# MalO_SAO_EasyEDA.net
KiCad netlist of a schematic drawn in EasyEDA Pro
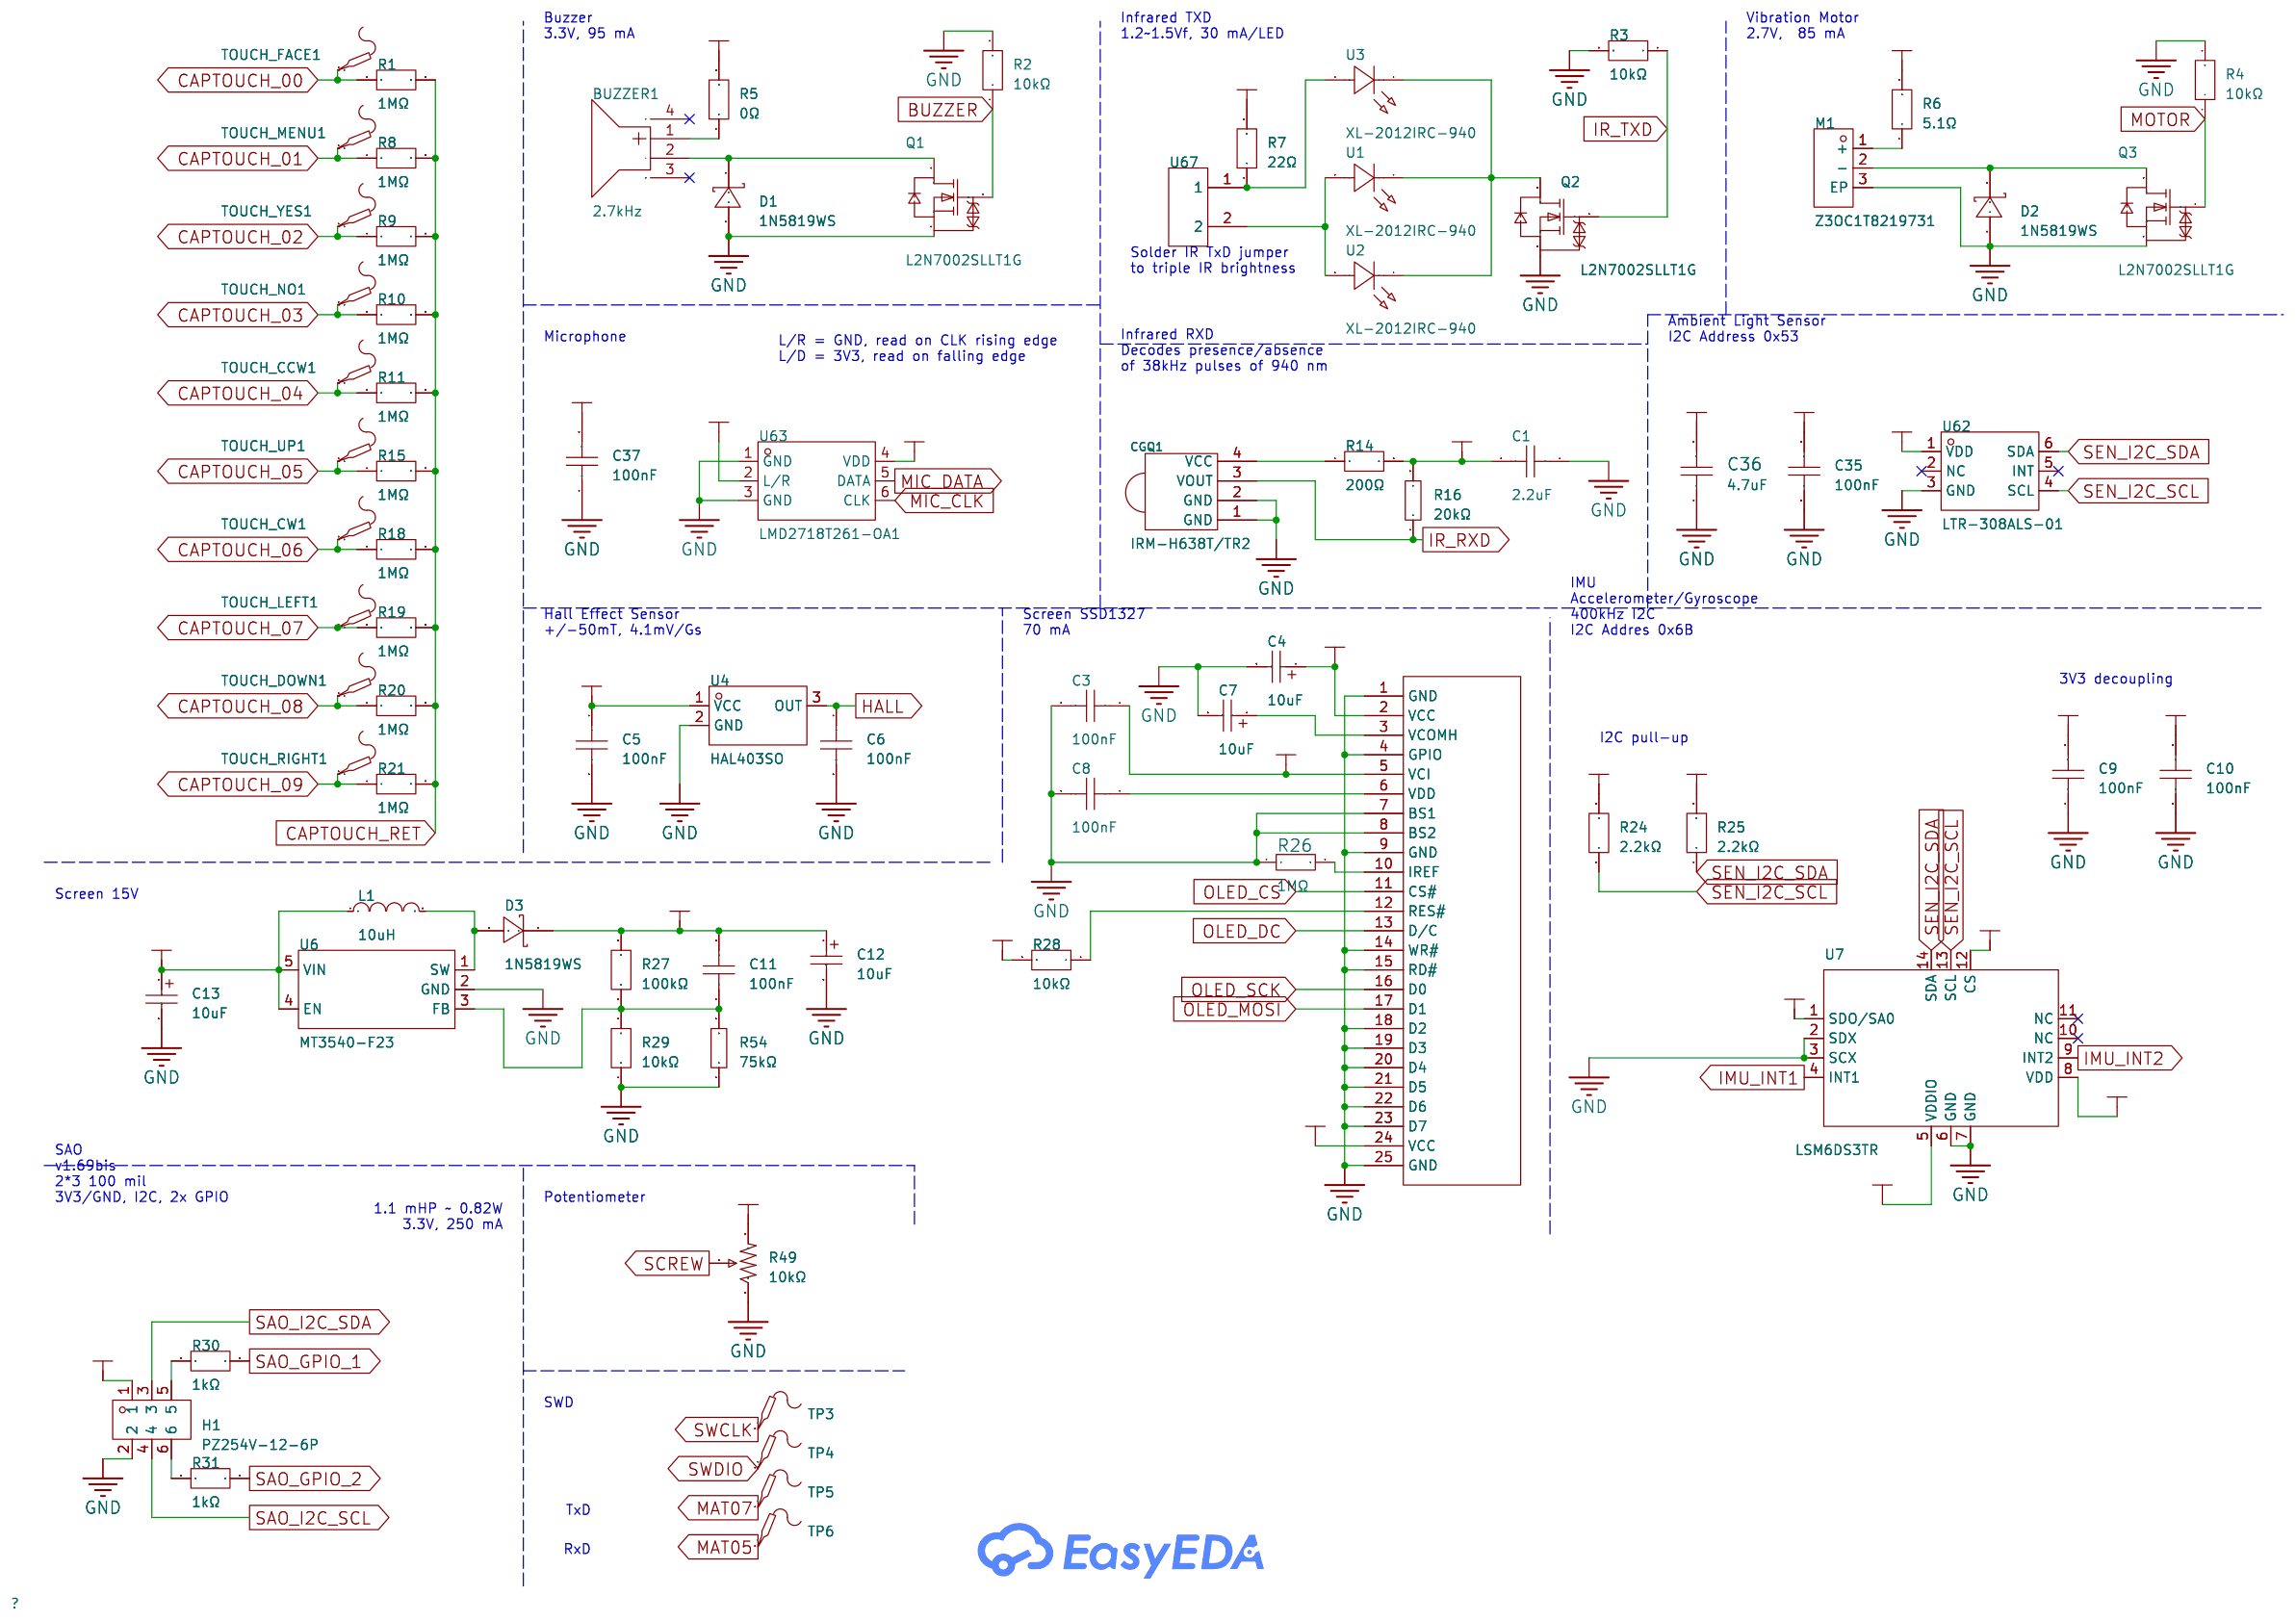
[diagram p0: Periphreals]
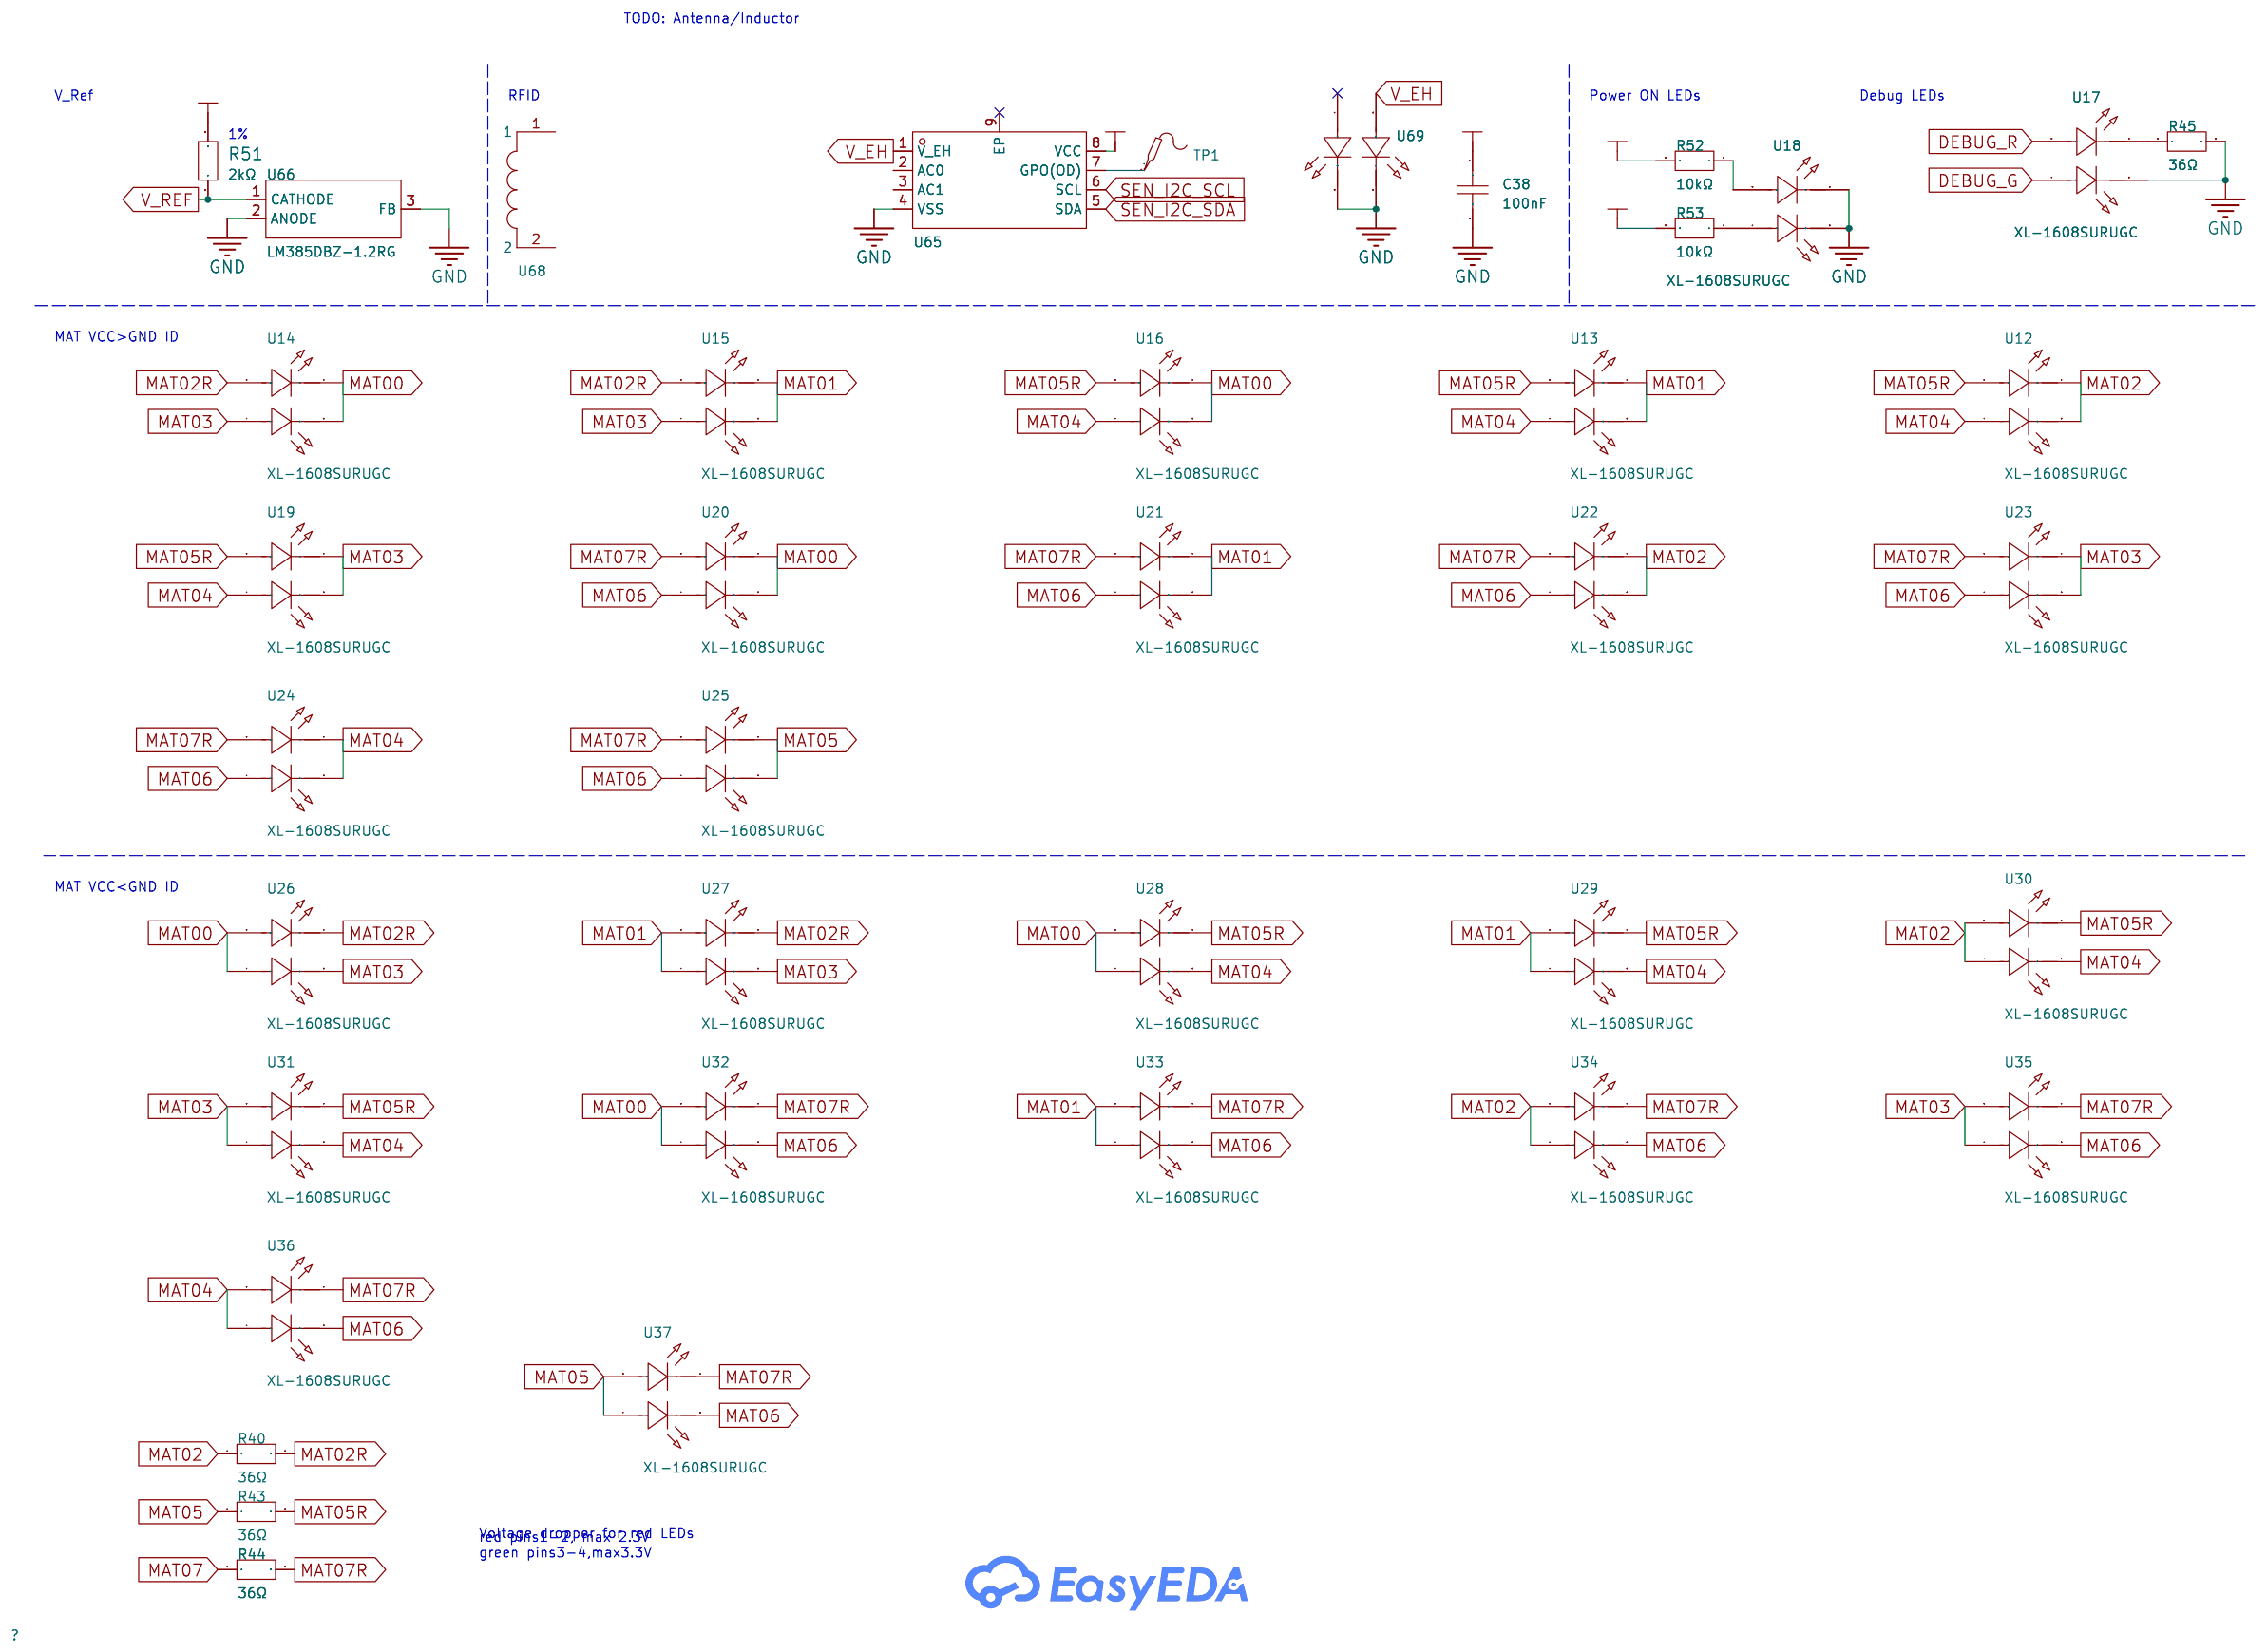
[diagram p1: LowerLED]
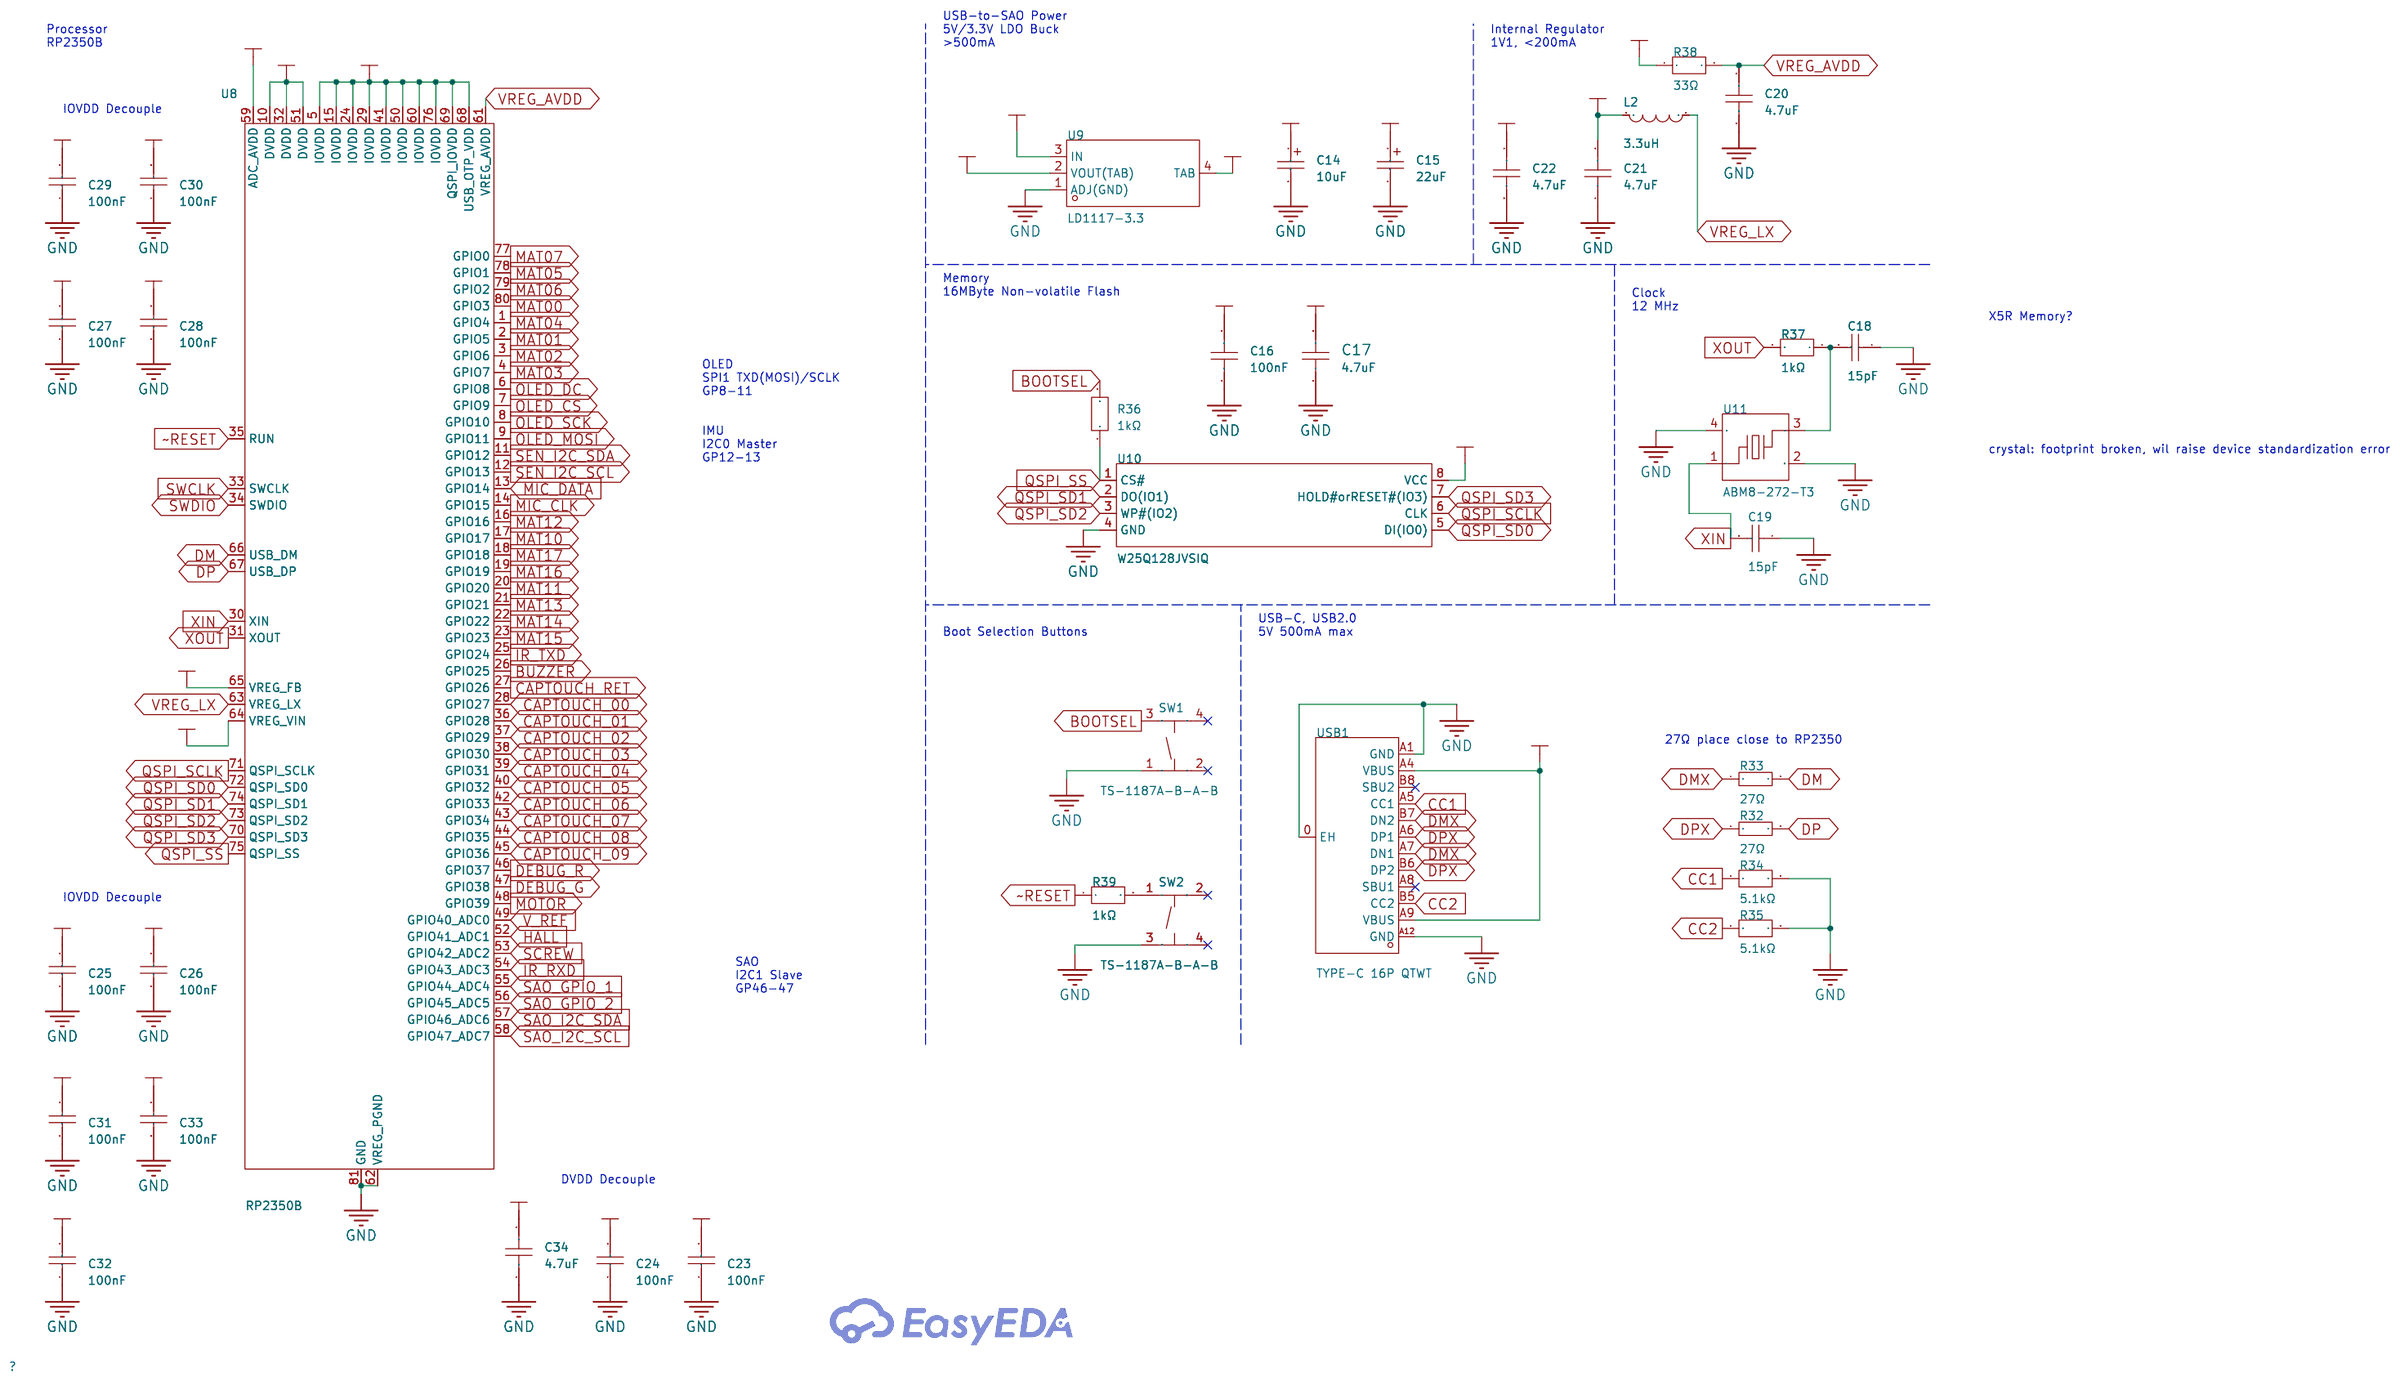
[diagram p2: Processor_Power]
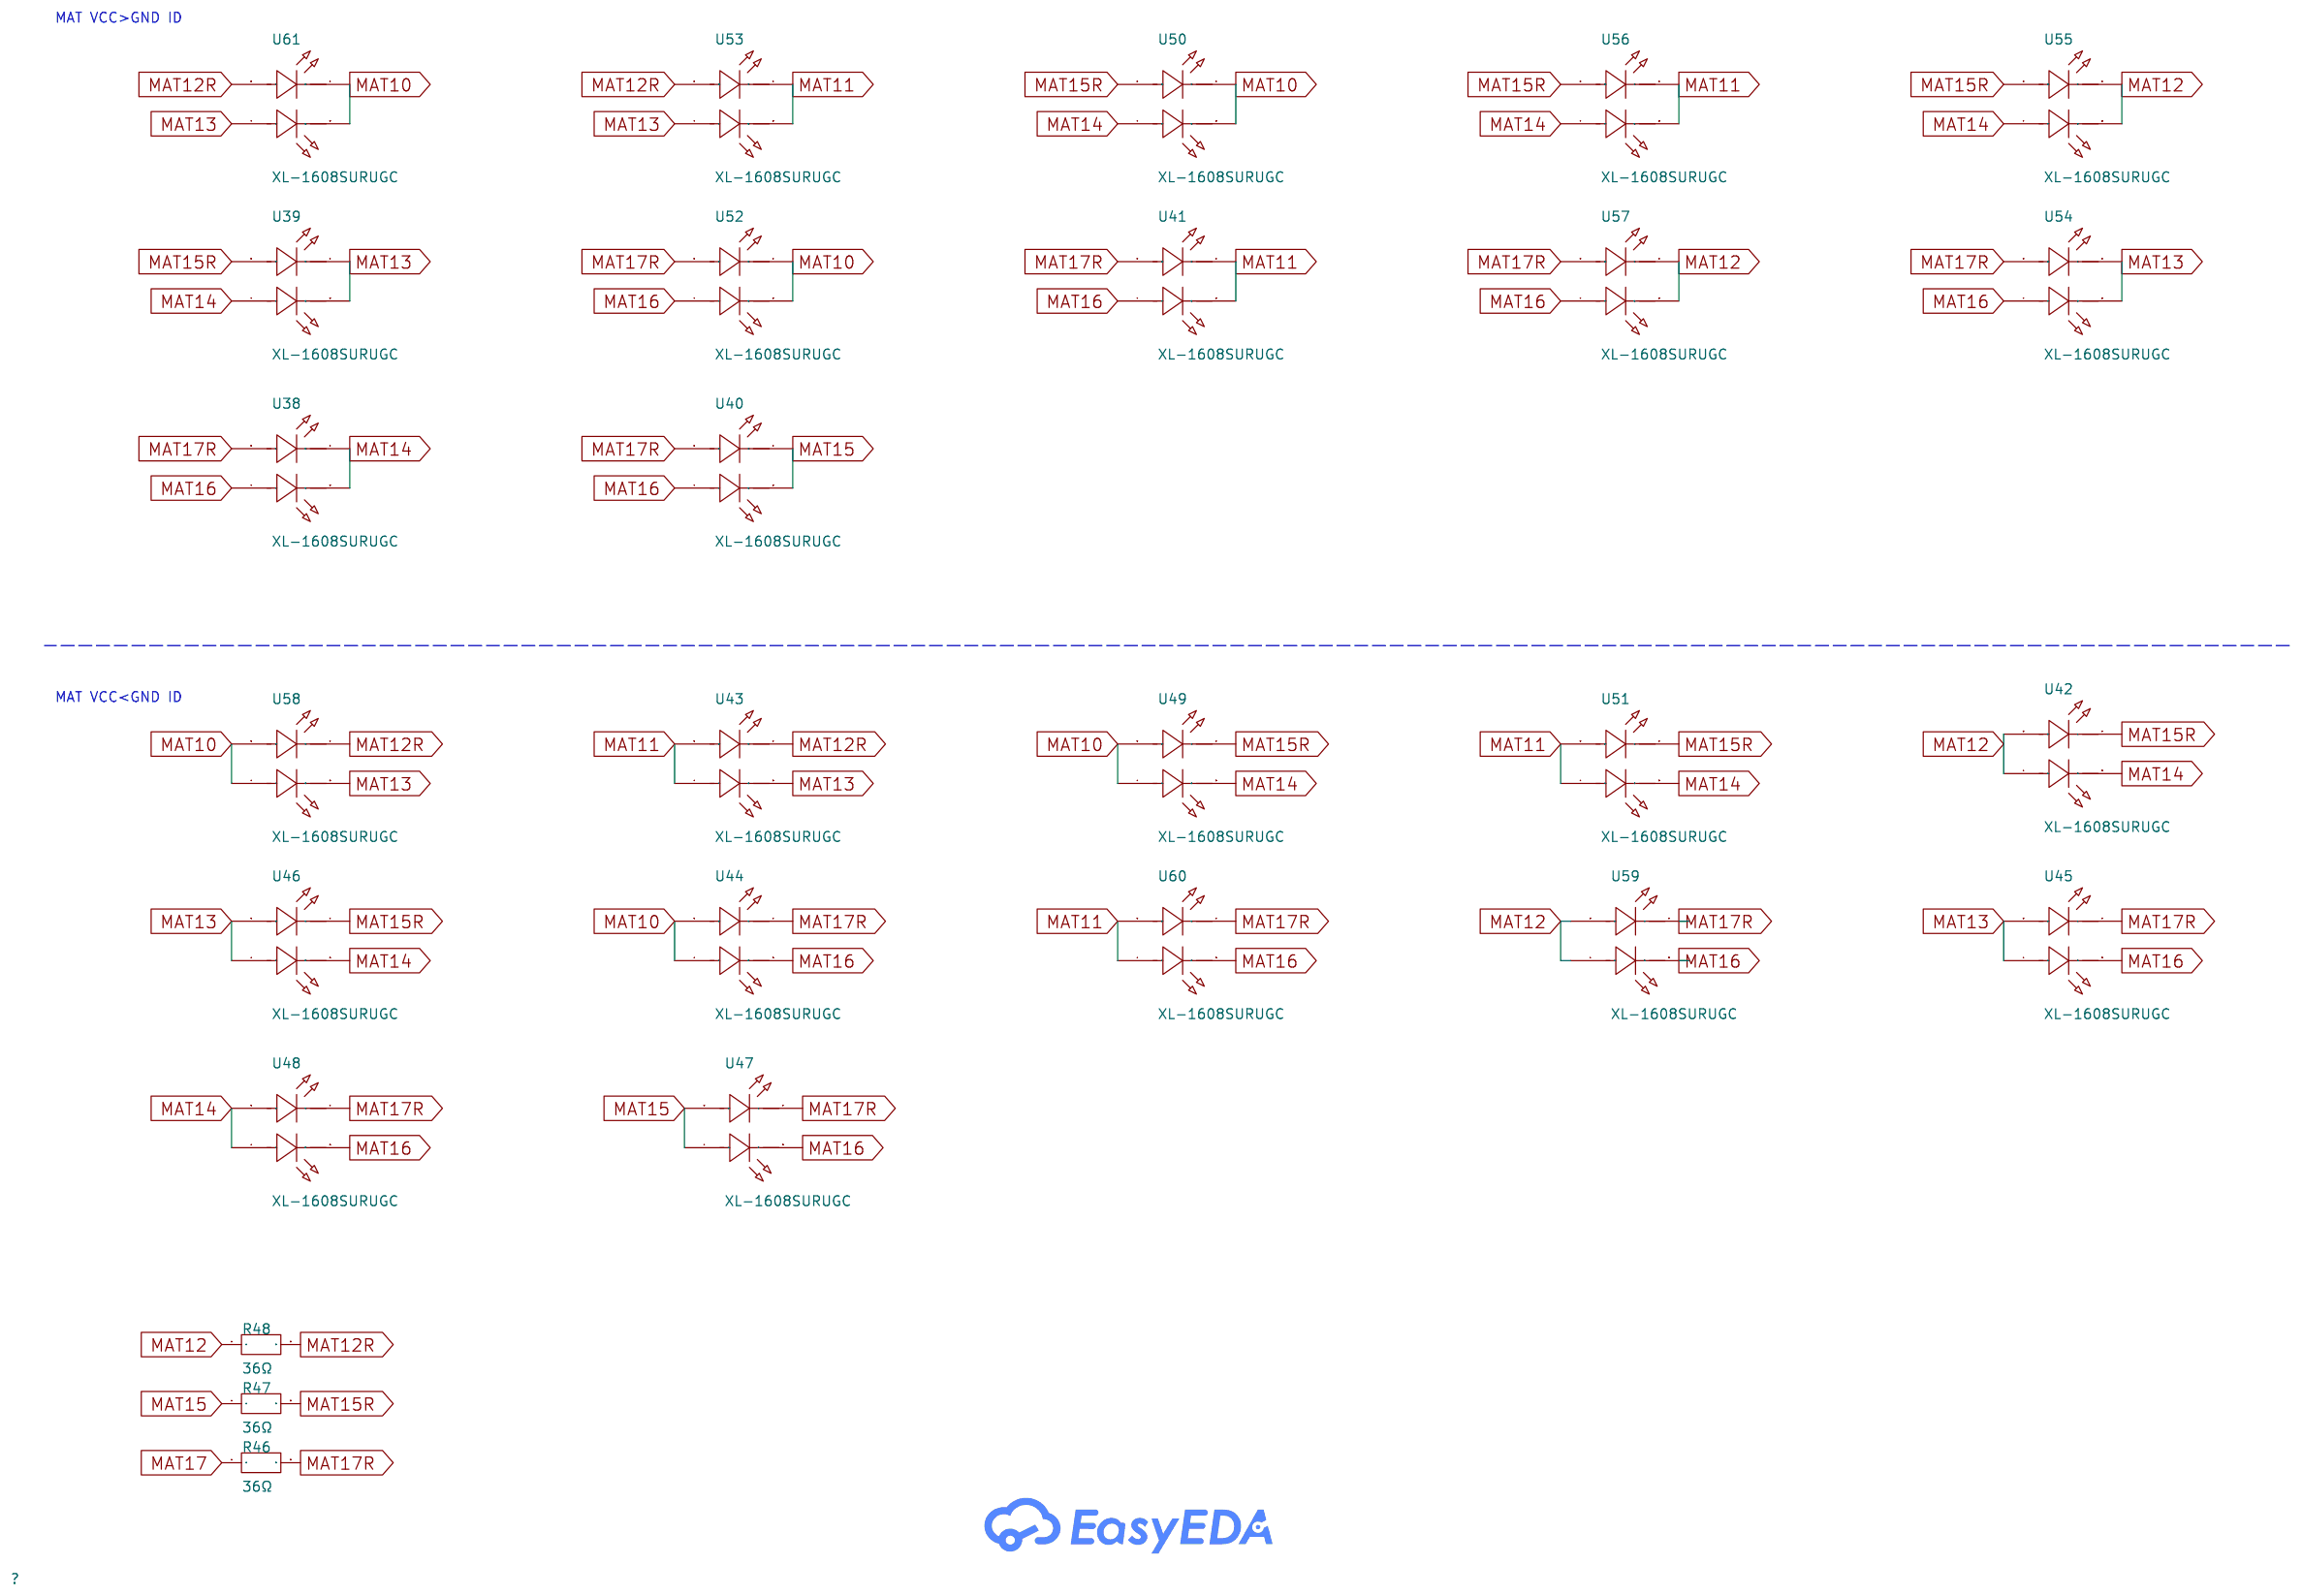
[diagram p3: UpperLED]

(export (version "E")
  (design (tool "Eeschema 10.0.6"))
  (components
    (comp (ref "BUZZER1")
      (value "2.7kHz")
      (footprint "easyedapro:BUZ-SMD_4P-L7.5-W7.5-P7.59-TL")
      (fields (field (name "Manufacturer Part") "MLT-7525") (field (name "Manufacturer") "华能"))
      (libsource (lib "easyedapro") (part "MLT-7525"))
    )
    (comp (ref "C1")
      (value "2.2uF")
      (footprint "easyedapro:C0402")
      (description "Capacitance:2.2uF Tolerance:±10% Tolerance:±10% Voltage Rating:10V Temperature Coefficient:X5R")
      (fields
        (field (name "Manufacturer Part") "CL05A225KP5NSNC")
        (field (name "Manufacturer") "SAMSUNG(三星)")
      )
      (libsource (lib "easyedapro") (part "CL05A225KP5NSNC"))
    )
    (comp (ref "C3")
      (value "100nF")
      (footprint "easyedapro:C0402")
      (description "Capacitance:100nF Tolerance:±10% Tolerance:±10% Voltage Rating:50V Temperature Coefficient:X7R")
      (fields
        (field (name "Manufacturer Part") "CL05B104KB54PNC")
        (field (name "Manufacturer") "SAMSUNG(三星)")
      )
      (libsource (lib "easyedapro") (part "CL05B104KB54PNC"))
    )
    (comp (ref "C4")
      (value "10uF")
      (footprint "easyedapro:CASE-A_3216")
      (fields (field (name "Manufacturer Part") "CA45-A010K106T") (field (name "Manufacturer") "湘怡中元/湘江"))
      (libsource (lib "easyedapro") (part "CA45-A010K106T"))
    )
    (comp (ref "C5")
      (value "100nF")
      (footprint "easyedapro:C0402")
      (description "Capacitance:100nF Tolerance:±10% Tolerance:±10% Voltage Rating:50V Temperature Coefficient:X7R")
      (fields
        (field (name "Manufacturer Part") "CL05B104KB54PNC")
        (field (name "Manufacturer") "SAMSUNG(三星)")
      )
      (libsource (lib "easyedapro") (part "CL05B104KB54PNC"))
    )
    (comp (ref "C6")
      (value "100nF")
      (footprint "easyedapro:C0402")
      (description "Capacitance:100nF Tolerance:±10% Tolerance:±10% Voltage Rating:50V Temperature Coefficient:X7R")
      (fields
        (field (name "Manufacturer Part") "CL05B104KB54PNC")
        (field (name "Manufacturer") "SAMSUNG(三星)")
      )
      (libsource (lib "easyedapro") (part "CL05B104KB54PNC"))
    )
    (comp (ref "C7")
      (value "10uF")
      (footprint "easyedapro:CASE-A_3216")
      (fields (field (name "Manufacturer Part") "CA45-A010K106T") (field (name "Manufacturer") "湘怡中元/湘江"))
      (libsource (lib "easyedapro") (part "CA45-A010K106T"))
    )
    (comp (ref "C8")
      (value "100nF")
      (footprint "easyedapro:C0402")
      (description "Capacitance:100nF Tolerance:±10% Tolerance:±10% Voltage Rating:50V Temperature Coefficient:X7R")
      (fields
        (field (name "Manufacturer Part") "CL05B104KB54PNC")
        (field (name "Manufacturer") "SAMSUNG(三星)")
      )
      (libsource (lib "easyedapro") (part "CL05B104KB54PNC"))
    )
    (comp (ref "C9")
      (value "100nF")
      (footprint "easyedapro:C0402")
      (description "Capacitance:100nF Tolerance:±10% Tolerance:±10% Voltage Rating:50V Temperature Coefficient:X7R")
      (fields
        (field (name "Manufacturer Part") "CL05B104KB54PNC")
        (field (name "Manufacturer") "SAMSUNG(三星)")
      )
      (libsource (lib "easyedapro") (part "CL05B104KB54PNC"))
    )
    (comp (ref "C10")
      (value "100nF")
      (footprint "easyedapro:C0402")
      (description "Capacitance:100nF Tolerance:±10% Tolerance:±10% Voltage Rating:50V Temperature Coefficient:X7R")
      (fields
        (field (name "Manufacturer Part") "CL05B104KB54PNC")
        (field (name "Manufacturer") "SAMSUNG(三星)")
      )
      (libsource (lib "easyedapro") (part "CL05B104KB54PNC"))
    )
    (comp (ref "C11")
      (value "100nF")
      (footprint "easyedapro:C0402")
      (description "Capacitance:100nF Tolerance:±10% Tolerance:±10% Voltage Rating:50V Temperature Coefficient:X7R")
      (fields
        (field (name "Manufacturer Part") "CL05B104KB54PNC")
        (field (name "Manufacturer") "SAMSUNG(三星)")
      )
      (libsource (lib "easyedapro") (part "CL05B104KB54PNC"))
    )
    (comp (ref "C12")
      (value "10uF")
      (footprint "easyedapro:CASE-A_3216")
      (fields (field (name "Manufacturer Part") "CA45-A010K106T") (field (name "Manufacturer") "湘怡中元/湘江"))
      (libsource (lib "easyedapro") (part "CA45-A010K106T"))
    )
    (comp (ref "C13")
      (value "10uF")
      (footprint "easyedapro:CASE-A_3216")
      (fields (field (name "Manufacturer Part") "CA45-A010K106T") (field (name "Manufacturer") "湘怡中元/湘江"))
      (libsource (lib "easyedapro") (part "CA45-A010K106T"))
    )
    (comp (ref "C35")
      (value "100nF")
      (footprint "easyedapro:C0402")
      (description "Capacitance:100nF Tolerance:±10% Tolerance:±10% Voltage Rating:50V Temperature Coefficient:X7R")
      (fields
        (field (name "Manufacturer Part") "CL05B104KB54PNC")
        (field (name "Manufacturer") "SAMSUNG(三星)")
      )
      (libsource (lib "easyedapro") (part "CL05B104KB54PNC"))
    )
    (comp (ref "C36")
      (value "4.7uF")
      (footprint "easyedapro:C0402")
      (description "Capacitance:4.7uF Tolerance:±10% Tolerance:±10% Voltage Rating:10V Temperature Coefficient:X5R")
      (fields
        (field (name "Manufacturer Part") "CL05A475KP5NRNC")
        (field (name "Manufacturer") "SAMSUNG(三星)")
      )
      (libsource (lib "easyedapro") (part "CL05A475KP5NRNC"))
    )
    (comp (ref "C37")
      (value "100nF")
      (footprint "easyedapro:C0402")
      (description "Capacitance:100nF Tolerance:±10% Tolerance:±10% Voltage Rating:50V Temperature Coefficient:X7R")
      (fields
        (field (name "Manufacturer Part") "CL05B104KB54PNC")
        (field (name "Manufacturer") "SAMSUNG(三星)")
      )
      (libsource (lib "easyedapro") (part "CL05B104KB54PNC"))
    )
    (comp (ref "CGQ1")
      (value "IRM-H638T/TR2")
      (footprint "easyedapro:SENSOR-SMD_IRM-H638T-TR2-TL")
      (fields (field (name "Manufacturer") "EVERLIGHT(亿光)"))
      (libsource (lib "easyedapro") (part "IRM-H638T/TR2"))
    )
    (comp (ref "D1")
      (value "1N5819WS")
      (footprint "easyedapro:SOD-323_L1.8-W1.3-LS2.5-RD")
      (fields (field (name "Manufacturer") "Hottech(合科泰)"))
      (libsource (lib "easyedapro") (part "1N5819WS"))
    )
    (comp (ref "D2")
      (value "1N5819WS")
      (footprint "easyedapro:SOD-323_L1.8-W1.3-LS2.5-RD")
      (fields (field (name "Manufacturer") "Hottech(合科泰)"))
      (libsource (lib "easyedapro") (part "1N5819WS"))
    )
    (comp (ref "D3")
      (value "1N5819WS")
      (footprint "easyedapro:SOD-323_L1.8-W1.3-LS2.5-RD")
      (fields (field (name "Manufacturer") "Hottech(合科泰)"))
      (libsource (lib "easyedapro") (part "1N5819WS"))
    )
    (comp (ref "H1")
      (value "PZ254V-12-6P")
      (footprint "easyedapro:HDR-TH_6P-P2.54-V-M-R2-C3-S2.54")
      (fields (field (name "Manufacturer") "XFCN(兴飞)"))
      (libsource (lib "easyedapro") (part "PZ254V-12-6P"))
    )
    (comp (ref "L1")
      (value "10uH")
      (footprint "easyedapro:L0603")
      (fields
        (field (name "Manufacturer Part") "SDFL1608S100KTF")
        (field (name "Manufacturer") "Sunlord(顺络)")
      )
      (libsource (lib "easyedapro") (part "SDFL1608S100KTF"))
    )
    (comp (ref "M1")
      (value "Z3OC1T8219731")
      (footprint "easyedapro:VIBRATING-MOTOR-SMD_3P-C9900001680")
      (fields (field (name "Manufacturer") "KOTL(金龙机电)"))
      (libsource (lib "easyedapro") (part "Z3OC1T8219731"))
    )
    (comp (ref "Q1")
      (value "L2N7002SLLT1G")
      (footprint "easyedapro:SOT-23-3_L3.0-W1.7-P0.95-LS2.9-BR")
      (fields (field (name "Manufacturer") "LRC(乐山无线电)"))
      (libsource (lib "easyedapro") (part "L2N7002SLLT1G"))
    )
    (comp (ref "Q2")
      (value "L2N7002SLLT1G")
      (footprint "easyedapro:SOT-23-3_L3.0-W1.7-P0.95-LS2.9-BR")
      (fields (field (name "Manufacturer") "LRC(乐山无线电)"))
      (libsource (lib "easyedapro") (part "L2N7002SLLT1G"))
    )
    (comp (ref "Q3")
      (value "L2N7002SLLT1G")
      (footprint "easyedapro:SOT-23-3_L3.0-W1.7-P0.95-LS2.9-BR")
      (fields (field (name "Manufacturer") "LRC(乐山无线电)"))
      (libsource (lib "easyedapro") (part "L2N7002SLLT1G"))
    )
    (comp (ref "R1")
      (value "1MΩ")
      (footprint "easyedapro:R0402")
      (fields (field (name "Manufacturer Part") "FRC0402F1004TS") (field (name "Manufacturer") "FOJAN(富捷)"))
      (libsource (lib "easyedapro") (part "FRC0402F1004TS"))
    )
    (comp (ref "R2")
      (value "10kΩ")
      (footprint "easyedapro:R0402")
      (fields (field (name "Manufacturer Part") "FRC0402J103 TS") (field (name "Manufacturer") "FOJAN(富捷)"))
      (libsource (lib "easyedapro") (part "FRC0402J103 TS"))
    )
    (comp (ref "R3")
      (value "10kΩ")
      (footprint "easyedapro:R0402")
      (fields (field (name "Manufacturer Part") "FRC0402J103 TS") (field (name "Manufacturer") "FOJAN(富捷)"))
      (libsource (lib "easyedapro") (part "FRC0402J103 TS"))
    )
    (comp (ref "R4")
      (value "10kΩ")
      (footprint "easyedapro:R0402")
      (fields (field (name "Manufacturer Part") "FRC0402J103 TS") (field (name "Manufacturer") "FOJAN(富捷)"))
      (libsource (lib "easyedapro") (part "FRC0402J103 TS"))
    )
    (comp (ref "R5")
      (value "0Ω")
      (footprint "easyedapro:R0402")
      (fields (field (name "Manufacturer Part") "FRC0402P000 TS") (field (name "Manufacturer") "FOJAN(富捷)"))
      (libsource (lib "easyedapro") (part "FRC0402P000 TS"))
    )
    (comp (ref "R6")
      (value "5.1Ω")
      (footprint "easyedapro:R0402")
      (fields (field (name "Manufacturer Part") "FRC0402F5R10TS") (field (name "Manufacturer") "FOJAN(富捷)"))
      (libsource (lib "easyedapro") (part "FRC0402F5R10TS"))
    )
    (comp (ref "R7")
      (value "22Ω")
      (footprint "easyedapro:R0805")
      (fields (field (name "Manufacturer Part") "AC0805FR-7W22RL") (field (name "Manufacturer") "YAGEO(国巨)"))
      (libsource (lib "easyedapro") (part "AC0805FR-7W22RL"))
    )
    (comp (ref "R8")
      (value "1MΩ")
      (footprint "easyedapro:R0402")
      (fields (field (name "Manufacturer Part") "FRC0402F1004TS") (field (name "Manufacturer") "FOJAN(富捷)"))
      (libsource (lib "easyedapro") (part "FRC0402F1004TS"))
    )
    (comp (ref "R9")
      (value "1MΩ")
      (footprint "easyedapro:R0402")
      (fields (field (name "Manufacturer Part") "FRC0402F1004TS") (field (name "Manufacturer") "FOJAN(富捷)"))
      (libsource (lib "easyedapro") (part "FRC0402F1004TS"))
    )
    (comp (ref "R10")
      (value "1MΩ")
      (footprint "easyedapro:R0402")
      (fields (field (name "Manufacturer Part") "FRC0402F1004TS") (field (name "Manufacturer") "FOJAN(富捷)"))
      (libsource (lib "easyedapro") (part "FRC0402F1004TS"))
    )
    (comp (ref "R11")
      (value "1MΩ")
      (footprint "easyedapro:R0402")
      (fields (field (name "Manufacturer Part") "FRC0402F1004TS") (field (name "Manufacturer") "FOJAN(富捷)"))
      (libsource (lib "easyedapro") (part "FRC0402F1004TS"))
    )
    (comp (ref "R14")
      (value "200Ω")
      (footprint "easyedapro:R0402")
      (fields (field (name "Manufacturer Part") "FRC0402F2000TS") (field (name "Manufacturer") "FOJAN(富捷)"))
      (libsource (lib "easyedapro") (part "FRC0402F2000TS"))
    )
    (comp (ref "R15")
      (value "1MΩ")
      (footprint "easyedapro:R0402")
      (fields (field (name "Manufacturer Part") "FRC0402F1004TS") (field (name "Manufacturer") "FOJAN(富捷)"))
      (libsource (lib "easyedapro") (part "FRC0402F1004TS"))
    )
    (comp (ref "R16")
      (value "20kΩ")
      (footprint "easyedapro:R0402")
      (fields (field (name "Manufacturer Part") "FRC0402F2002TS") (field (name "Manufacturer") "FOJAN(富捷)"))
      (libsource (lib "easyedapro") (part "FRC0402F2002TS"))
    )
    (comp (ref "R18")
      (value "1MΩ")
      (footprint "easyedapro:R0402")
      (fields (field (name "Manufacturer Part") "FRC0402F1004TS") (field (name "Manufacturer") "FOJAN(富捷)"))
      (libsource (lib "easyedapro") (part "FRC0402F1004TS"))
    )
    (comp (ref "R19")
      (value "1MΩ")
      (footprint "easyedapro:R0402")
      (fields (field (name "Manufacturer Part") "FRC0402F1004TS") (field (name "Manufacturer") "FOJAN(富捷)"))
      (libsource (lib "easyedapro") (part "FRC0402F1004TS"))
    )
    (comp (ref "R20")
      (value "1MΩ")
      (footprint "easyedapro:R0402")
      (fields (field (name "Manufacturer Part") "FRC0402F1004TS") (field (name "Manufacturer") "FOJAN(富捷)"))
      (libsource (lib "easyedapro") (part "FRC0402F1004TS"))
    )
    (comp (ref "R21")
      (value "1MΩ")
      (footprint "easyedapro:R0402")
      (fields (field (name "Manufacturer Part") "FRC0402F1004TS") (field (name "Manufacturer") "FOJAN(富捷)"))
      (libsource (lib "easyedapro") (part "FRC0402F1004TS"))
    )
    (comp (ref "R24")
      (value "2.2kΩ")
      (footprint "easyedapro:R0402")
      (fields (field (name "Manufacturer Part") "FRC0402J222 TS") (field (name "Manufacturer") "FOJAN(富捷)"))
      (libsource (lib "easyedapro") (part "FRC0402J222 TS"))
    )
    (comp (ref "R25")
      (value "2.2kΩ")
      (footprint "easyedapro:R0402")
      (fields (field (name "Manufacturer Part") "FRC0402J222 TS") (field (name "Manufacturer") "FOJAN(富捷)"))
      (libsource (lib "easyedapro") (part "FRC0402J222 TS"))
    )
    (comp (ref "R26")
      (value "1MΩ")
      (footprint "easyedapro:R0402")
      (fields
        (field (name "Manufacturer Part") "0402WGF1004TCE")
        (field (name "Manufacturer") "UNI-ROYAL(厚声)")
      )
      (libsource (lib "easyedapro") (part "0402WGF1004TCE"))
    )
    (comp (ref "R27")
      (value "100kΩ")
      (footprint "easyedapro:R0402")
      (fields (field (name "Manufacturer Part") "FRC0402J104 TS") (field (name "Manufacturer") "FOJAN(富捷)"))
      (libsource (lib "easyedapro") (part "FRC0402J104 TS"))
    )
    (comp (ref "R28")
      (value "10kΩ")
      (footprint "easyedapro:R0402")
      (fields (field (name "Manufacturer Part") "FRC0402J103 TS") (field (name "Manufacturer") "FOJAN(富捷)"))
      (libsource (lib "easyedapro") (part "FRC0402J103 TS"))
    )
    (comp (ref "R29")
      (value "10kΩ")
      (footprint "easyedapro:R0402")
      (fields (field (name "Manufacturer Part") "FRC0402J103 TS") (field (name "Manufacturer") "FOJAN(富捷)"))
      (libsource (lib "easyedapro") (part "FRC0402J103 TS"))
    )
    (comp (ref "R30")
      (value "1kΩ")
      (footprint "easyedapro:R0402")
      (fields (field (name "Manufacturer Part") "FRC0402F1001TS") (field (name "Manufacturer") "FOJAN(富捷)"))
      (libsource (lib "easyedapro") (part "FRC0402F1001TS"))
    )
    (comp (ref "R31")
      (value "1kΩ")
      (footprint "easyedapro:R0402")
      (fields (field (name "Manufacturer Part") "FRC0402F1001TS") (field (name "Manufacturer") "FOJAN(富捷)"))
      (libsource (lib "easyedapro") (part "FRC0402F1001TS"))
    )
    (comp (ref "R49")
      (value "10kΩ")
      (footprint "easyedapro:RES-ADJ-SMD_3P-L3.0-W3.8-P1.75-BR")
      (fields (field (name "Manufacturer Part") "TC33X-2-103E") (field (name "Manufacturer") "BOURNS"))
      (libsource (lib "easyedapro") (part "TC33X-2-103E"))
    )
    (comp (ref "R54")
      (value "75kΩ")
      (footprint "easyedapro:R0402")
      (fields
        (field (name "Manufacturer Part") "0402WGF7502TCE")
        (field (name "Manufacturer") "UNI-ROYAL(厚声)")
      )
      (libsource (lib "easyedapro") (part "0402WGF7502TCE"))
    )
    (comp (ref "TOUCH_CCW1")
      (value "~")
      (footprint "easyedapro:Test-Point-0.5mm")
      (description "Test Point 测试点")
      (libsource (lib "easyedapro") (part "Test-Point"))
    )
    (comp (ref "TOUCH_CW1")
      (value "~")
      (footprint "easyedapro:Test-Point-0.5mm")
      (description "Test Point 测试点")
      (libsource (lib "easyedapro") (part "Test-Point"))
    )
    (comp (ref "TOUCH_DOWN1")
      (value "~")
      (footprint "easyedapro:Test-Point-0.5mm")
      (description "Test Point 测试点")
      (libsource (lib "easyedapro") (part "Test-Point"))
    )
    (comp (ref "TOUCH_FACE1")
      (value "~")
      (footprint "easyedapro:Test-Point-0.5mm")
      (description "Test Point 测试点")
      (libsource (lib "easyedapro") (part "Test-Point"))
    )
    (comp (ref "TOUCH_LEFT1")
      (value "~")
      (footprint "easyedapro:Test-Point-0.5mm")
      (description "Test Point 测试点")
      (libsource (lib "easyedapro") (part "Test-Point"))
    )
    (comp (ref "TOUCH_MENU1")
      (value "~")
      (footprint "easyedapro:Test-Point-0.5mm")
      (description "Test Point 测试点")
      (libsource (lib "easyedapro") (part "Test-Point"))
    )
    (comp (ref "TOUCH_NO1")
      (value "~")
      (footprint "easyedapro:Test-Point-0.5mm")
      (description "Test Point 测试点")
      (libsource (lib "easyedapro") (part "Test-Point"))
    )
    (comp (ref "TOUCH_RIGHT1")
      (value "~")
      (footprint "easyedapro:Test-Point-0.5mm")
      (description "Test Point 测试点")
      (libsource (lib "easyedapro") (part "Test-Point"))
    )
    (comp (ref "TOUCH_UP1")
      (value "~")
      (footprint "easyedapro:Test-Point-0.5mm")
      (description "Test Point 测试点")
      (libsource (lib "easyedapro") (part "Test-Point"))
    )
    (comp (ref "TOUCH_YES1")
      (value "~")
      (footprint "easyedapro:Test-Point-0.5mm")
      (description "Test Point 测试点")
      (libsource (lib "easyedapro") (part "Test-Point"))
    )
    (comp (ref "TP3")
      (value "~")
      (footprint "easyedapro:Test-Point-0.5mm")
      (description "Test Point 测试点")
      (libsource (lib "easyedapro") (part "Test-Point"))
    )
    (comp (ref "TP4")
      (value "~")
      (footprint "easyedapro:Test-Point-0.5mm")
      (description "Test Point 测试点")
      (libsource (lib "easyedapro") (part "Test-Point"))
    )
    (comp (ref "TP5")
      (value "~")
      (footprint "easyedapro:Test-Point-0.5mm")
      (description "Test Point 测试点")
      (libsource (lib "easyedapro") (part "Test-Point"))
    )
    (comp (ref "TP6")
      (value "~")
      (footprint "easyedapro:Test-Point-0.5mm")
      (description "Test Point 测试点")
      (libsource (lib "easyedapro") (part "Test-Point"))
    )
    (comp (ref "U1")
      (value "XL-2012IRC-940")
      (footprint "easyedapro:LED0805-RD")
      (fields (field (name "Manufacturer") "XINGLIGHT(成兴光)"))
      (libsource (lib "easyedapro") (part "XL-2012IRC-940"))
    )
    (comp (ref "U2")
      (value "XL-2012IRC-940")
      (footprint "easyedapro:LED0805-RD")
      (fields (field (name "Manufacturer") "XINGLIGHT(成兴光)"))
      (libsource (lib "easyedapro") (part "XL-2012IRC-940"))
    )
    (comp (ref "U3")
      (value "XL-2012IRC-940")
      (footprint "easyedapro:LED0805-RD")
      (fields (field (name "Manufacturer") "XINGLIGHT(成兴光)"))
      (libsource (lib "easyedapro") (part "XL-2012IRC-940"))
    )
    (comp (ref "U4")
      (value "HAL403SO")
      (footprint "easyedapro:SOT-23-3_L2.9-W1.3-P1.90-LS2.4-BR-CW")
      (fields (field (name "Manufacturer") "Hallwee(霍尔微电子)"))
      (libsource (lib "easyedapro") (part "HAL403SO"))
    )
    (comp (ref "U5") (value "~") (libsource (lib "easyedapro") (part "SSD1327_128x128")))
    (comp (ref "U6")
      (value "MT3540-F23")
      (footprint "easyedapro:SOT-23-5_L3.0-W1.7-P0.95-LS2.8-BR")
      (fields (field (name "Manufacturer") "西安航天民芯"))
      (libsource (lib "easyedapro") (part "MT3540-F23"))
    )
    (comp (ref "U7")
      (value "LSM6DS3TR")
      (footprint "easyedapro:LGA-14_L3.0-W2.5-P0.50-TL")
      (fields (field (name "Manufacturer") "ST(意法半导体)"))
      (libsource (lib "easyedapro") (part "LSM6DS3TR"))
    )
    (comp (ref "U62")
      (value "LTR-308ALS-01")
      (footprint "easyedapro:SENSOR-SMD_6P-L2.0-W2.0-P0.65-BL")
      (fields (field (name "Manufacturer") "LITEON(光宝)"))
      (libsource (lib "easyedapro") (part "LTR-308ALS-01"))
    )
    (comp (ref "U63")
      (value "LMD2718T261-OA1")
      (footprint "easyedapro:MIC-SMD_6P-L2.8-W1.9-P0.98-TL")
      (fields (field (name "Manufacturer") "LinkMems(聆麦声学)"))
      (libsource (lib "easyedapro") (part "LMD2718T261-OA1"))
    )
    (comp (ref "U67") (value "~") (libsource (lib "easyedapro") (part "open_solder_jumper")))
    (comp (ref "C38")
      (value "100nF")
      (footprint "easyedapro:C0402")
      (description "Capacitance:100nF Tolerance:±10% Tolerance:±10% Voltage Rating:50V Temperature Coefficient:X7R")
      (fields
        (field (name "Manufacturer Part") "CL05B104KB54PNC")
        (field (name "Manufacturer") "SAMSUNG(三星)")
      )
      (libsource (lib "easyedapro") (part "CL05B104KB54PNC"))
    )
    (comp (ref "R40")
      (value "36Ω")
      (footprint "easyedapro:R0402")
      (fields (field (name "Manufacturer Part") "FRC0402F36R0TS") (field (name "Manufacturer") "FOJAN(富捷)"))
      (libsource (lib "easyedapro") (part "FRC0402F36R0TS"))
    )
    (comp (ref "R43")
      (value "36Ω")
      (footprint "easyedapro:R0402")
      (fields (field (name "Manufacturer Part") "FRC0402F36R0TS") (field (name "Manufacturer") "FOJAN(富捷)"))
      (libsource (lib "easyedapro") (part "FRC0402F36R0TS"))
    )
    (comp (ref "R44")
      (value "36Ω")
      (footprint "easyedapro:R0402")
      (fields (field (name "Manufacturer Part") "FRC0402F36R0TS") (field (name "Manufacturer") "FOJAN(富捷)"))
      (libsource (lib "easyedapro") (part "FRC0402F36R0TS"))
    )
    (comp (ref "R45")
      (value "36Ω")
      (footprint "easyedapro:R0402")
      (fields (field (name "Manufacturer Part") "FRC0402F36R0TS") (field (name "Manufacturer") "FOJAN(富捷)"))
      (libsource (lib "easyedapro") (part "FRC0402F36R0TS"))
    )
    (comp (ref "R51")
      (value "2kΩ")
      (footprint "easyedapro:R0402")
      (fields (field (name "Manufacturer Part") "FRC0402F2001TS") (field (name "Manufacturer") "FOJAN(富捷)"))
      (libsource (lib "easyedapro") (part "FRC0402F2001TS"))
    )
    (comp (ref "R52")
      (value "10kΩ")
      (footprint "easyedapro:R0402")
      (fields (field (name "Manufacturer Part") "FRC0402J103 TS") (field (name "Manufacturer") "FOJAN(富捷)"))
      (libsource (lib "easyedapro") (part "FRC0402J103 TS"))
    )
    (comp (ref "R53")
      (value "10kΩ")
      (footprint "easyedapro:R0402")
      (fields (field (name "Manufacturer Part") "FRC0402J103 TS") (field (name "Manufacturer") "FOJAN(富捷)"))
      (libsource (lib "easyedapro") (part "FRC0402J103 TS"))
    )
    (comp (ref "TP1")
      (value "~")
      (footprint "easyedapro:Test-Point-0.5mm")
      (description "Test Point 测试点")
      (libsource (lib "easyedapro") (part "Test-Point"))
    )
    (comp (ref "U12")
      (value "XL-1608SURUGC")
      (footprint "easyedapro:LED-SMD_4P-L1.6-W0.8-RD_1")
      (fields (field (name "Manufacturer") "XINGLIGHT(成兴光)"))
      (libsource (lib "easyedapro") (part "XL-1608SURUGC"))
    )
    (comp (ref "U13")
      (value "XL-1608SURUGC")
      (footprint "easyedapro:LED-SMD_4P-L1.6-W0.8-RD_1")
      (fields (field (name "Manufacturer") "XINGLIGHT(成兴光)"))
      (libsource (lib "easyedapro") (part "XL-1608SURUGC"))
    )
    (comp (ref "U14")
      (value "XL-1608SURUGC")
      (footprint "easyedapro:LED-SMD_4P-L1.6-W0.8-RD_1")
      (fields (field (name "Manufacturer") "XINGLIGHT(成兴光)"))
      (libsource (lib "easyedapro") (part "XL-1608SURUGC"))
    )
    (comp (ref "U15")
      (value "XL-1608SURUGC")
      (footprint "easyedapro:LED-SMD_4P-L1.6-W0.8-RD_1")
      (fields (field (name "Manufacturer") "XINGLIGHT(成兴光)"))
      (libsource (lib "easyedapro") (part "XL-1608SURUGC"))
    )
    (comp (ref "U16")
      (value "XL-1608SURUGC")
      (footprint "easyedapro:LED-SMD_4P-L1.6-W0.8-RD_1")
      (fields (field (name "Manufacturer") "XINGLIGHT(成兴光)"))
      (libsource (lib "easyedapro") (part "XL-1608SURUGC"))
    )
    (comp (ref "U17")
      (value "XL-1608SURUGC")
      (footprint "easyedapro:LED-SMD_4P-L1.6-W0.8-RD_1")
      (fields (field (name "Manufacturer") "XINGLIGHT(成兴光)"))
      (libsource (lib "easyedapro") (part "XL-1608SURUGC"))
    )
    (comp (ref "U18")
      (value "XL-1608SURUGC")
      (footprint "easyedapro:LED-SMD_4P-L1.6-W0.8-RD_1")
      (fields (field (name "Manufacturer") "XINGLIGHT(成兴光)"))
      (libsource (lib "easyedapro") (part "XL-1608SURUGC"))
    )
    (comp (ref "U19")
      (value "XL-1608SURUGC")
      (footprint "easyedapro:LED-SMD_4P-L1.6-W0.8-RD_1")
      (fields (field (name "Manufacturer") "XINGLIGHT(成兴光)"))
      (libsource (lib "easyedapro") (part "XL-1608SURUGC"))
    )
    (comp (ref "U20")
      (value "XL-1608SURUGC")
      (footprint "easyedapro:LED-SMD_4P-L1.6-W0.8-RD_1")
      (fields (field (name "Manufacturer") "XINGLIGHT(成兴光)"))
      (libsource (lib "easyedapro") (part "XL-1608SURUGC"))
    )
    (comp (ref "U21")
      (value "XL-1608SURUGC")
      (footprint "easyedapro:LED-SMD_4P-L1.6-W0.8-RD_1")
      (fields (field (name "Manufacturer") "XINGLIGHT(成兴光)"))
      (libsource (lib "easyedapro") (part "XL-1608SURUGC"))
    )
    (comp (ref "U22")
      (value "XL-1608SURUGC")
      (footprint "easyedapro:LED-SMD_4P-L1.6-W0.8-RD_1")
      (fields (field (name "Manufacturer") "XINGLIGHT(成兴光)"))
      (libsource (lib "easyedapro") (part "XL-1608SURUGC"))
    )
    (comp (ref "U23")
      (value "XL-1608SURUGC")
      (footprint "easyedapro:LED-SMD_4P-L1.6-W0.8-RD_1")
      (fields (field (name "Manufacturer") "XINGLIGHT(成兴光)"))
      (libsource (lib "easyedapro") (part "XL-1608SURUGC"))
    )
    (comp (ref "U24")
      (value "XL-1608SURUGC")
      (footprint "easyedapro:LED-SMD_4P-L1.6-W0.8-RD_1")
      (fields (field (name "Manufacturer") "XINGLIGHT(成兴光)"))
      (libsource (lib "easyedapro") (part "XL-1608SURUGC"))
    )
    (comp (ref "U25")
      (value "XL-1608SURUGC")
      (footprint "easyedapro:LED-SMD_4P-L1.6-W0.8-RD_1")
      (fields (field (name "Manufacturer") "XINGLIGHT(成兴光)"))
      (libsource (lib "easyedapro") (part "XL-1608SURUGC"))
    )
    (comp (ref "U26")
      (value "XL-1608SURUGC")
      (footprint "easyedapro:LED-SMD_4P-L1.6-W0.8-RD_1")
      (fields (field (name "Manufacturer") "XINGLIGHT(成兴光)"))
      (libsource (lib "easyedapro") (part "XL-1608SURUGC"))
    )
    (comp (ref "U27")
      (value "XL-1608SURUGC")
      (footprint "easyedapro:LED-SMD_4P-L1.6-W0.8-RD_1")
      (fields (field (name "Manufacturer") "XINGLIGHT(成兴光)"))
      (libsource (lib "easyedapro") (part "XL-1608SURUGC"))
    )
    (comp (ref "U28")
      (value "XL-1608SURUGC")
      (footprint "easyedapro:LED-SMD_4P-L1.6-W0.8-RD_1")
      (fields (field (name "Manufacturer") "XINGLIGHT(成兴光)"))
      (libsource (lib "easyedapro") (part "XL-1608SURUGC"))
    )
    (comp (ref "U29")
      (value "XL-1608SURUGC")
      (footprint "easyedapro:LED-SMD_4P-L1.6-W0.8-RD_1")
      (fields (field (name "Manufacturer") "XINGLIGHT(成兴光)"))
      (libsource (lib "easyedapro") (part "XL-1608SURUGC"))
    )
    (comp (ref "U30")
      (value "XL-1608SURUGC")
      (footprint "easyedapro:LED-SMD_4P-L1.6-W0.8-RD_1")
      (fields (field (name "Manufacturer") "XINGLIGHT(成兴光)"))
      (libsource (lib "easyedapro") (part "XL-1608SURUGC"))
    )
    (comp (ref "U31")
      (value "XL-1608SURUGC")
      (footprint "easyedapro:LED-SMD_4P-L1.6-W0.8-RD_1")
      (fields (field (name "Manufacturer") "XINGLIGHT(成兴光)"))
      (libsource (lib "easyedapro") (part "XL-1608SURUGC"))
    )
    (comp (ref "U32")
      (value "XL-1608SURUGC")
      (footprint "easyedapro:LED-SMD_4P-L1.6-W0.8-RD_1")
      (fields (field (name "Manufacturer") "XINGLIGHT(成兴光)"))
      (libsource (lib "easyedapro") (part "XL-1608SURUGC"))
    )
    (comp (ref "U33")
      (value "XL-1608SURUGC")
      (footprint "easyedapro:LED-SMD_4P-L1.6-W0.8-RD_1")
      (fields (field (name "Manufacturer") "XINGLIGHT(成兴光)"))
      (libsource (lib "easyedapro") (part "XL-1608SURUGC"))
    )
    (comp (ref "U34")
      (value "XL-1608SURUGC")
      (footprint "easyedapro:LED-SMD_4P-L1.6-W0.8-RD_1")
      (fields (field (name "Manufacturer") "XINGLIGHT(成兴光)"))
      (libsource (lib "easyedapro") (part "XL-1608SURUGC"))
    )
    (comp (ref "U35")
      (value "XL-1608SURUGC")
      (footprint "easyedapro:LED-SMD_4P-L1.6-W0.8-RD_1")
      (fields (field (name "Manufacturer") "XINGLIGHT(成兴光)"))
      (libsource (lib "easyedapro") (part "XL-1608SURUGC"))
    )
    (comp (ref "U36")
      (value "XL-1608SURUGC")
      (footprint "easyedapro:LED-SMD_4P-L1.6-W0.8-RD_1")
      (fields (field (name "Manufacturer") "XINGLIGHT(成兴光)"))
      (libsource (lib "easyedapro") (part "XL-1608SURUGC"))
    )
    (comp (ref "U37")
      (value "XL-1608SURUGC")
      (footprint "easyedapro:LED-SMD_4P-L1.6-W0.8-RD_1")
      (fields (field (name "Manufacturer") "XINGLIGHT(成兴光)"))
      (libsource (lib "easyedapro") (part "XL-1608SURUGC"))
    )
    (comp (ref "U65")
      (value "13.56MHz")
      (footprint "easyedapro:UFDFN-8_L3.0-W2.0-P0.50-TL-EP1.4")
      (fields (field (name "Manufacturer Part") "ST25DV04K-IER6C3") (field (name "Manufacturer") "ST(意法半导体)"))
      (libsource (lib "easyedapro") (part "ST25DV04K-IER6C3"))
    )
    (comp (ref "U66")
      (value "LM385DBZ-1.2RG")
      (footprint "easyedapro:SOT-23-3_L2.9-W1.6-P1.90-LS2.8-BR")
      (fields (field (name "Manufacturer") "HGC(深圳汉芯)"))
      (libsource (lib "easyedapro") (part "LM385DBZ-1.2RG"))
    )
    (comp (ref "U68") (value "~") (libsource (lib "easyedapro") (part "rfid_antenna")))
    (comp (ref "U69")
      (value "XL-1608SURUGC")
      (footprint "easyedapro:LED-SMD_4P-L1.6-W0.8-RD_1")
      (fields (field (name "Manufacturer") "XINGLIGHT(成兴光)"))
      (libsource (lib "easyedapro") (part "XL-1608SURUGC"))
    )
    (comp (ref "C14")
      (value "10uF")
      (footprint "easyedapro:CASE-A_3216")
      (fields (field (name "Manufacturer Part") "CA45-A010K106T") (field (name "Manufacturer") "湘怡中元/湘江"))
      (libsource (lib "easyedapro") (part "CA45-A010K106T"))
    )
    (comp (ref "C15")
      (value "22uF")
      (footprint "easyedapro:CASE-A_3216")
      (fields
        (field (name "Manufacturer Part") "CA45-A-10V-22uF-K")
        (field (name "Manufacturer") "CEC(振华新云)")
      )
      (libsource (lib "easyedapro") (part "CA45-A-10V-22UF-K"))
    )
    (comp (ref "C16")
      (value "100nF")
      (footprint "easyedapro:C0402")
      (description "Capacitance:100nF Tolerance:±10% Tolerance:±10% Voltage Rating:50V Temperature Coefficient:X7R")
      (fields
        (field (name "Manufacturer Part") "CL05B104KB54PNC")
        (field (name "Manufacturer") "SAMSUNG(三星)")
      )
      (libsource (lib "easyedapro") (part "CL05B104KB54PNC"))
    )
    (comp (ref "C17")
      (value "4.7uF")
      (footprint "easyedapro:C0402")
      (description "Capacitance:4.7uF Tolerance:±10% Tolerance:±10% Voltage Rating:10V Temperature Coefficient:X5R")
      (fields
        (field (name "Manufacturer Part") "CL05A475KP5NRNC")
        (field (name "Manufacturer") "SAMSUNG(三星)")
      )
      (libsource (lib "easyedapro") (part "CL05A475KP5NRNC"))
    )
    (comp (ref "C18")
      (value "15pF")
      (footprint "easyedapro:C0402")
      (description "Capacitance:15pF Tolerance:±5% Tolerance:±5% Voltage Rating:50V Temperature Coefficient:C0G")
      (fields (field (name "Manufacturer Part") "0402CG150J500NT") (field (name "Manufacturer") "FH(风华)"))
      (libsource (lib "easyedapro") (part "0402CG150J500NT"))
    )
    (comp (ref "C19")
      (value "15pF")
      (footprint "easyedapro:C0402")
      (description "Capacitance:15pF Tolerance:±5% Tolerance:±5% Voltage Rating:50V Temperature Coefficient:C0G")
      (fields (field (name "Manufacturer Part") "0402CG150J500NT") (field (name "Manufacturer") "FH(风华)"))
      (libsource (lib "easyedapro") (part "0402CG150J500NT"))
    )
    (comp (ref "C20")
      (value "4.7uF")
      (footprint "easyedapro:C0402")
      (description "Capacitance:4.7uF Tolerance:±20% Tolerance:±20% Voltage Rating:10V Temperature Coefficient:X5R")
      (fields
        (field (name "Manufacturer Part") "CL05A475MP5NRNC")
        (field (name "Manufacturer") "SAMSUNG(三星)")
      )
      (libsource (lib "easyedapro") (part "CL05A475MP5NRNC"))
    )
    (comp (ref "C21")
      (value "4.7uF")
      (footprint "easyedapro:C0402")
      (description "Capacitance:4.7uF Tolerance:±20% Tolerance:±20% Voltage Rating:10V Temperature Coefficient:X5R")
      (fields
        (field (name "Manufacturer Part") "CL05A475MP5NRNC")
        (field (name "Manufacturer") "SAMSUNG(三星)")
      )
      (libsource (lib "easyedapro") (part "CL05A475MP5NRNC"))
    )
    (comp (ref "C22")
      (value "4.7uF")
      (footprint "easyedapro:C0402")
      (description "Capacitance:4.7uF Tolerance:±20% Tolerance:±20% Voltage Rating:10V Temperature Coefficient:X5R")
      (fields
        (field (name "Manufacturer Part") "CL05A475MP5NRNC")
        (field (name "Manufacturer") "SAMSUNG(三星)")
      )
      (libsource (lib "easyedapro") (part "CL05A475MP5NRNC"))
    )
    (comp (ref "C23")
      (value "100nF")
      (footprint "easyedapro:C0402")
      (description "Capacitance:100nF Tolerance:±10% Tolerance:±10% Voltage Rating:25V Temperature Coefficient:X5R")
      (fields
        (field (name "Manufacturer Part") "CL05A104KA5NNNC")
        (field (name "Manufacturer") "SAMSUNG(三星)")
      )
      (libsource (lib "easyedapro") (part "CL05A104KA5NNNC"))
    )
    (comp (ref "C24")
      (value "100nF")
      (footprint "easyedapro:C0402")
      (description "Capacitance:100nF Tolerance:±10% Tolerance:±10% Voltage Rating:25V Temperature Coefficient:X5R")
      (fields
        (field (name "Manufacturer Part") "CL05A104KA5NNNC")
        (field (name "Manufacturer") "SAMSUNG(三星)")
      )
      (libsource (lib "easyedapro") (part "CL05A104KA5NNNC"))
    )
    (comp (ref "C25")
      (value "100nF")
      (footprint "easyedapro:C0402")
      (description "Capacitance:100nF Tolerance:±10% Tolerance:±10% Voltage Rating:25V Temperature Coefficient:X5R")
      (fields
        (field (name "Manufacturer Part") "CL05A104KA5NNNC")
        (field (name "Manufacturer") "SAMSUNG(三星)")
      )
      (libsource (lib "easyedapro") (part "CL05A104KA5NNNC"))
    )
    (comp (ref "C26")
      (value "100nF")
      (footprint "easyedapro:C0402")
      (description "Capacitance:100nF Tolerance:±10% Tolerance:±10% Voltage Rating:25V Temperature Coefficient:X5R")
      (fields
        (field (name "Manufacturer Part") "CL05A104KA5NNNC")
        (field (name "Manufacturer") "SAMSUNG(三星)")
      )
      (libsource (lib "easyedapro") (part "CL05A104KA5NNNC"))
    )
    (comp (ref "C27")
      (value "100nF")
      (footprint "easyedapro:C0402")
      (description "Capacitance:100nF Tolerance:±10% Tolerance:±10% Voltage Rating:25V Temperature Coefficient:X5R")
      (fields
        (field (name "Manufacturer Part") "CL05A104KA5NNNC")
        (field (name "Manufacturer") "SAMSUNG(三星)")
      )
      (libsource (lib "easyedapro") (part "CL05A104KA5NNNC"))
    )
    (comp (ref "C28")
      (value "100nF")
      (footprint "easyedapro:C0402")
      (description "Capacitance:100nF Tolerance:±10% Tolerance:±10% Voltage Rating:25V Temperature Coefficient:X5R")
      (fields
        (field (name "Manufacturer Part") "CL05A104KA5NNNC")
        (field (name "Manufacturer") "SAMSUNG(三星)")
      )
      (libsource (lib "easyedapro") (part "CL05A104KA5NNNC"))
    )
    (comp (ref "C29")
      (value "100nF")
      (footprint "easyedapro:C0402")
      (description "Capacitance:100nF Tolerance:±10% Tolerance:±10% Voltage Rating:25V Temperature Coefficient:X5R")
      (fields
        (field (name "Manufacturer Part") "CL05A104KA5NNNC")
        (field (name "Manufacturer") "SAMSUNG(三星)")
      )
      (libsource (lib "easyedapro") (part "CL05A104KA5NNNC"))
    )
    (comp (ref "C30")
      (value "100nF")
      (footprint "easyedapro:C0402")
      (description "Capacitance:100nF Tolerance:±10% Tolerance:±10% Voltage Rating:25V Temperature Coefficient:X5R")
      (fields
        (field (name "Manufacturer Part") "CL05A104KA5NNNC")
        (field (name "Manufacturer") "SAMSUNG(三星)")
      )
      (libsource (lib "easyedapro") (part "CL05A104KA5NNNC"))
    )
    (comp (ref "C31")
      (value "100nF")
      (footprint "easyedapro:C0402")
      (description "Capacitance:100nF Tolerance:±10% Tolerance:±10% Voltage Rating:25V Temperature Coefficient:X5R")
      (fields
        (field (name "Manufacturer Part") "CL05A104KA5NNNC")
        (field (name "Manufacturer") "SAMSUNG(三星)")
      )
      (libsource (lib "easyedapro") (part "CL05A104KA5NNNC"))
    )
    (comp (ref "C32")
      (value "100nF")
      (footprint "easyedapro:C0402")
      (description "Capacitance:100nF Tolerance:±10% Tolerance:±10% Voltage Rating:25V Temperature Coefficient:X5R")
      (fields
        (field (name "Manufacturer Part") "CL05A104KA5NNNC")
        (field (name "Manufacturer") "SAMSUNG(三星)")
      )
      (libsource (lib "easyedapro") (part "CL05A104KA5NNNC"))
    )
    (comp (ref "C33")
      (value "100nF")
      (footprint "easyedapro:C0402")
      (description "Capacitance:100nF Tolerance:±10% Tolerance:±10% Voltage Rating:25V Temperature Coefficient:X5R")
      (fields
        (field (name "Manufacturer Part") "CL05A104KA5NNNC")
        (field (name "Manufacturer") "SAMSUNG(三星)")
      )
      (libsource (lib "easyedapro") (part "CL05A104KA5NNNC"))
    )
    (comp (ref "C34")
      (value "4.7uF")
      (footprint "easyedapro:C0402")
      (description "Capacitance:4.7uF Tolerance:±20% Tolerance:±20% Voltage Rating:10V Temperature Coefficient:X5R")
      (fields
        (field (name "Manufacturer Part") "CL05A475MP5NRNC")
        (field (name "Manufacturer") "SAMSUNG(三星)")
      )
      (libsource (lib "easyedapro") (part "CL05A475MP5NRNC"))
    )
    (comp (ref "L2")
      (value "3.3uH")
      (footprint "easyedapro:IND-SMD_L2.0-W1.6_AOTA-B201610S3R3-101-T")
      (fields
        (field (name "Manufacturer Part") "AOTA-B201610S3R3-101-T")
        (field (name "Manufacturer") "ABRACON")
      )
      (libsource (lib "easyedapro") (part "AOTA-B201610S3R3-101-T"))
    )
    (comp (ref "R32")
      (value "27Ω")
      (footprint "easyedapro:R0603")
      (fields
        (field (name "Manufacturer Part") "0603WAF270JT5E")
        (field (name "Manufacturer") "UNI-ROYAL(厚声)")
      )
      (libsource (lib "easyedapro") (part "0603WAF270JT5E"))
    )
    (comp (ref "R33")
      (value "27Ω")
      (footprint "easyedapro:R0603")
      (fields
        (field (name "Manufacturer Part") "0603WAF270JT5E")
        (field (name "Manufacturer") "UNI-ROYAL(厚声)")
      )
      (libsource (lib "easyedapro") (part "0603WAF270JT5E"))
    )
    (comp (ref "R34")
      (value "5.1kΩ")
      (footprint "easyedapro:R0603")
      (fields (field (name "Manufacturer Part") "FRC0603F5101TS") (field (name "Manufacturer") "FOJAN(富捷)"))
      (libsource (lib "easyedapro") (part "FRC0603F5101TS"))
    )
    (comp (ref "R35")
      (value "5.1kΩ")
      (footprint "easyedapro:R0603")
      (fields (field (name "Manufacturer Part") "FRC0603F5101TS") (field (name "Manufacturer") "FOJAN(富捷)"))
      (libsource (lib "easyedapro") (part "FRC0603F5101TS"))
    )
    (comp (ref "R36")
      (value "1kΩ")
      (footprint "easyedapro:R0402")
      (fields (field (name "Manufacturer Part") "FRC0402F1001TS") (field (name "Manufacturer") "FOJAN(富捷)"))
      (libsource (lib "easyedapro") (part "FRC0402F1001TS"))
    )
    (comp (ref "R37")
      (value "1kΩ")
      (footprint "easyedapro:R0402")
      (fields (field (name "Manufacturer Part") "FRC0402F1001TS") (field (name "Manufacturer") "FOJAN(富捷)"))
      (libsource (lib "easyedapro") (part "FRC0402F1001TS"))
    )
    (comp (ref "R38")
      (value "33Ω")
      (footprint "easyedapro:R0402")
      (fields (field (name "Manufacturer Part") "FRC0402F33R0TS") (field (name "Manufacturer") "FOJAN(富捷)"))
      (libsource (lib "easyedapro") (part "FRC0402F33R0TS"))
    )
    (comp (ref "R39")
      (value "1kΩ")
      (footprint "easyedapro:R0402")
      (fields (field (name "Manufacturer Part") "FRC0402F1001TS") (field (name "Manufacturer") "FOJAN(富捷)"))
      (libsource (lib "easyedapro") (part "FRC0402F1001TS"))
    )
    (comp (ref "SW1")
      (value "TS-1187A-B-A-B")
      (footprint "easyedapro:SW-SMD_4P-L5.1-W5.1-P3.70-LS6.5-TL_H1.5")
      (fields (field (name "Manufacturer") "XKB Connection(中国星坤)"))
      (libsource (lib "easyedapro") (part "TS-1187A-B-A-B"))
    )
    (comp (ref "SW2")
      (value "TS-1187A-B-A-B")
      (footprint "easyedapro:SW-SMD_4P-L5.1-W5.1-P3.70-LS6.5-TL_H1.5")
      (fields (field (name "Manufacturer") "XKB Connection(中国星坤)"))
      (libsource (lib "easyedapro") (part "TS-1187A-B-A-B"))
    )
    (comp (ref "U8")
      (value "RP2350B")
      (footprint "easyedapro:QFN-80_L10.0-W10.0-P0.40-TL-EP3.4")
      (fields (field (name "Manufacturer") "Raspberry Pi(树莓派)"))
      (libsource (lib "easyedapro") (part "RP2350B_C42415655"))
    )
    (comp (ref "U9")
      (value "LD1117-3.3")
      (footprint "easyedapro:SOT-223_L6.7-W3.5-P2.30-BR")
      (fields (field (name "Manufacturer") "UMW(友台半导体)"))
      (libsource (lib "easyedapro") (part "LD1117-3.3"))
    )
    (comp (ref "U10")
      (value "W25Q128JVSIQ")
      (footprint "easyedapro:SOIC-8_L5.3-W5.3-P1.27-LS8.0-BL")
      (fields (field (name "Manufacturer") "Winbond(华邦)"))
      (libsource (lib "easyedapro") (part "W25Q128JVSIQ"))
    )
    (comp (ref "U11")
      (value "ABM8-272-T3")
      (fields (field (name "Manufacturer") "ABRACON"))
      (libsource (lib "easyedapro") (part "ABM8-272-T3_C20625731"))
    )
    (comp (ref "USB1")
      (value "TYPE-C 16P QTWT")
      (footprint "easyedapro:USB-TYPE-C-SMD_TYPE-C-16P-QTWT")
      (fields (field (name "Manufacturer") "SHOU HAN(首韩)"))
      (libsource (lib "easyedapro") (part "TYPE-C 16P QTWT"))
    )
    (comp (ref "R46")
      (value "36Ω")
      (footprint "easyedapro:R0402")
      (fields (field (name "Manufacturer Part") "FRC0402F36R0TS") (field (name "Manufacturer") "FOJAN(富捷)"))
      (libsource (lib "easyedapro") (part "FRC0402F36R0TS"))
    )
    (comp (ref "R47")
      (value "36Ω")
      (footprint "easyedapro:R0402")
      (fields (field (name "Manufacturer Part") "FRC0402F36R0TS") (field (name "Manufacturer") "FOJAN(富捷)"))
      (libsource (lib "easyedapro") (part "FRC0402F36R0TS"))
    )
    (comp (ref "R48")
      (value "36Ω")
      (footprint "easyedapro:R0402")
      (fields (field (name "Manufacturer Part") "FRC0402F36R0TS") (field (name "Manufacturer") "FOJAN(富捷)"))
      (libsource (lib "easyedapro") (part "FRC0402F36R0TS"))
    )
    (comp (ref "U38")
      (value "XL-1608SURUGC")
      (footprint "easyedapro:LED-SMD_4P-L1.6-W0.8-RD_1")
      (fields (field (name "Manufacturer") "XINGLIGHT(成兴光)"))
      (libsource (lib "easyedapro") (part "XL-1608SURUGC"))
    )
    (comp (ref "U39")
      (value "XL-1608SURUGC")
      (footprint "easyedapro:LED-SMD_4P-L1.6-W0.8-RD_1")
      (fields (field (name "Manufacturer") "XINGLIGHT(成兴光)"))
      (libsource (lib "easyedapro") (part "XL-1608SURUGC"))
    )
    (comp (ref "U40")
      (value "XL-1608SURUGC")
      (footprint "easyedapro:LED-SMD_4P-L1.6-W0.8-RD_1")
      (fields (field (name "Manufacturer") "XINGLIGHT(成兴光)"))
      (libsource (lib "easyedapro") (part "XL-1608SURUGC"))
    )
    (comp (ref "U41")
      (value "XL-1608SURUGC")
      (footprint "easyedapro:LED-SMD_4P-L1.6-W0.8-RD_1")
      (fields (field (name "Manufacturer") "XINGLIGHT(成兴光)"))
      (libsource (lib "easyedapro") (part "XL-1608SURUGC"))
    )
    (comp (ref "U42")
      (value "XL-1608SURUGC")
      (footprint "easyedapro:LED-SMD_4P-L1.6-W0.8-RD_1")
      (fields (field (name "Manufacturer") "XINGLIGHT(成兴光)"))
      (libsource (lib "easyedapro") (part "XL-1608SURUGC"))
    )
    (comp (ref "U43")
      (value "XL-1608SURUGC")
      (footprint "easyedapro:LED-SMD_4P-L1.6-W0.8-RD_1")
      (fields (field (name "Manufacturer") "XINGLIGHT(成兴光)"))
      (libsource (lib "easyedapro") (part "XL-1608SURUGC"))
    )
    (comp (ref "U44")
      (value "XL-1608SURUGC")
      (footprint "easyedapro:LED-SMD_4P-L1.6-W0.8-RD_1")
      (fields (field (name "Manufacturer") "XINGLIGHT(成兴光)"))
      (libsource (lib "easyedapro") (part "XL-1608SURUGC"))
    )
    (comp (ref "U45")
      (value "XL-1608SURUGC")
      (footprint "easyedapro:LED-SMD_4P-L1.6-W0.8-RD_1")
      (fields (field (name "Manufacturer") "XINGLIGHT(成兴光)"))
      (libsource (lib "easyedapro") (part "XL-1608SURUGC"))
    )
    (comp (ref "U46")
      (value "XL-1608SURUGC")
      (footprint "easyedapro:LED-SMD_4P-L1.6-W0.8-RD_1")
      (fields (field (name "Manufacturer") "XINGLIGHT(成兴光)"))
      (libsource (lib "easyedapro") (part "XL-1608SURUGC"))
    )
    (comp (ref "U47")
      (value "XL-1608SURUGC")
      (footprint "easyedapro:LED-SMD_4P-L1.6-W0.8-RD_1")
      (fields (field (name "Manufacturer") "XINGLIGHT(成兴光)"))
      (libsource (lib "easyedapro") (part "XL-1608SURUGC"))
    )
    (comp (ref "U48")
      (value "XL-1608SURUGC")
      (footprint "easyedapro:LED-SMD_4P-L1.6-W0.8-RD_1")
      (fields (field (name "Manufacturer") "XINGLIGHT(成兴光)"))
      (libsource (lib "easyedapro") (part "XL-1608SURUGC"))
    )
    (comp (ref "U49")
      (value "XL-1608SURUGC")
      (footprint "easyedapro:LED-SMD_4P-L1.6-W0.8-RD_1")
      (fields (field (name "Manufacturer") "XINGLIGHT(成兴光)"))
      (libsource (lib "easyedapro") (part "XL-1608SURUGC"))
    )
    (comp (ref "U50")
      (value "XL-1608SURUGC")
      (footprint "easyedapro:LED-SMD_4P-L1.6-W0.8-RD_1")
      (fields (field (name "Manufacturer") "XINGLIGHT(成兴光)"))
      (libsource (lib "easyedapro") (part "XL-1608SURUGC"))
    )
    (comp (ref "U51")
      (value "XL-1608SURUGC")
      (footprint "easyedapro:LED-SMD_4P-L1.6-W0.8-RD_1")
      (fields (field (name "Manufacturer") "XINGLIGHT(成兴光)"))
      (libsource (lib "easyedapro") (part "XL-1608SURUGC"))
    )
    (comp (ref "U52")
      (value "XL-1608SURUGC")
      (footprint "easyedapro:LED-SMD_4P-L1.6-W0.8-RD_1")
      (fields (field (name "Manufacturer") "XINGLIGHT(成兴光)"))
      (libsource (lib "easyedapro") (part "XL-1608SURUGC"))
    )
    (comp (ref "U53")
      (value "XL-1608SURUGC")
      (footprint "easyedapro:LED-SMD_4P-L1.6-W0.8-RD_1")
      (fields (field (name "Manufacturer") "XINGLIGHT(成兴光)"))
      (libsource (lib "easyedapro") (part "XL-1608SURUGC"))
    )
    (comp (ref "U54")
      (value "XL-1608SURUGC")
      (footprint "easyedapro:LED-SMD_4P-L1.6-W0.8-RD_1")
      (fields (field (name "Manufacturer") "XINGLIGHT(成兴光)"))
      (libsource (lib "easyedapro") (part "XL-1608SURUGC"))
    )
    (comp (ref "U55")
      (value "XL-1608SURUGC")
      (footprint "easyedapro:LED-SMD_4P-L1.6-W0.8-RD_1")
      (fields (field (name "Manufacturer") "XINGLIGHT(成兴光)"))
      (libsource (lib "easyedapro") (part "XL-1608SURUGC"))
    )
    (comp (ref "U56")
      (value "XL-1608SURUGC")
      (footprint "easyedapro:LED-SMD_4P-L1.6-W0.8-RD_1")
      (fields (field (name "Manufacturer") "XINGLIGHT(成兴光)"))
      (libsource (lib "easyedapro") (part "XL-1608SURUGC"))
    )
    (comp (ref "U57")
      (value "XL-1608SURUGC")
      (footprint "easyedapro:LED-SMD_4P-L1.6-W0.8-RD_1")
      (fields (field (name "Manufacturer") "XINGLIGHT(成兴光)"))
      (libsource (lib "easyedapro") (part "XL-1608SURUGC"))
    )
    (comp (ref "U58")
      (value "XL-1608SURUGC")
      (footprint "easyedapro:LED-SMD_4P-L1.6-W0.8-RD_1")
      (fields (field (name "Manufacturer") "XINGLIGHT(成兴光)"))
      (libsource (lib "easyedapro") (part "XL-1608SURUGC"))
    )
    (comp (ref "U59")
      (value "XL-1608SURUGC")
      (footprint "easyedapro:LED-SMD_4P-L1.6-W0.8-RD_1")
      (fields (field (name "Manufacturer") "XINGLIGHT(成兴光)"))
      (libsource (lib "easyedapro") (part "XL-1608SURUGC"))
    )
    (comp (ref "U60")
      (value "XL-1608SURUGC")
      (footprint "easyedapro:LED-SMD_4P-L1.6-W0.8-RD_1")
      (fields (field (name "Manufacturer") "XINGLIGHT(成兴光)"))
      (libsource (lib "easyedapro") (part "XL-1608SURUGC"))
    )
    (comp (ref "U61")
      (value "XL-1608SURUGC")
      (footprint "easyedapro:LED-SMD_4P-L1.6-W0.8-RD_1")
      (fields (field (name "Manufacturer") "XINGLIGHT(成兴光)"))
      (libsource (lib "easyedapro") (part "XL-1608SURUGC"))
    )
  )
  (nets
    (net (code "1") (name "+1V1") (class "Default")
      (node (ref "C21") (pin "2") (pinfunction "2_2") (pintype "unspecified"))
      (node (ref "C23") (pin "2") (pinfunction "2_2") (pintype "input"))
      (node (ref "C24") (pin "2") (pinfunction "2_2") (pintype "input"))
      (node (ref "C34") (pin "1") (pinfunction "1_1") (pintype "unspecified"))
      (node (ref "L2") (pin "2") (pinfunction "2_2") (pintype "unspecified"))
      (node (ref "U8") (pin "10") (pinfunction "DVDD_10") (pintype "unspecified"))
      (node (ref "U8") (pin "32") (pinfunction "DVDD_32") (pintype "unspecified"))
      (node (ref "U8") (pin "51") (pinfunction "DVDD_51") (pintype "unspecified"))
      (node (ref "U8") (pin "65") (pinfunction "VREG_FB_65") (pintype "unspecified"))
    )
    (net (code "2") (name "+3V3") (class "Default")
      (node (ref "C1") (pin "2") (pinfunction "2_2") (pintype "unspecified"))
      (node (ref "C10") (pin "2") (pinfunction "2_2") (pintype "input"))
      (node (ref "C13") (pin "1") (pinfunction "1_1") (pintype "input"))
      (node (ref "C15") (pin "1") (pinfunction "1_1") (pintype "input"))
      (node (ref "C16") (pin "2") (pinfunction "2_2") (pintype "input"))
      (node (ref "C17") (pin "2") (pinfunction "2_2") (pintype "input"))
      (node (ref "C22") (pin "1") (pinfunction "1_1") (pintype "unspecified"))
      (node (ref "C25") (pin "2") (pinfunction "2_2") (pintype "input"))
      (node (ref "C26") (pin "2") (pinfunction "2_2") (pintype "input"))
      (node (ref "C27") (pin "2") (pinfunction "2_2") (pintype "input"))
      (node (ref "C28") (pin "2") (pinfunction "2_2") (pintype "input"))
      (node (ref "C29") (pin "2") (pinfunction "2_2") (pintype "input"))
      (node (ref "C3") (pin "1") (pinfunction "1_1") (pintype "input"))
      (node (ref "C30") (pin "2") (pinfunction "2_2") (pintype "input"))
      (node (ref "C31") (pin "2") (pinfunction "2_2") (pintype "input"))
      (node (ref "C32") (pin "2") (pinfunction "2_2") (pintype "input"))
      (node (ref "C33") (pin "2") (pinfunction "2_2") (pintype "input"))
      (node (ref "C35") (pin "2") (pinfunction "2_2") (pintype "input"))
      (node (ref "C36") (pin "2") (pinfunction "2_2") (pintype "input"))
      (node (ref "C37") (pin "2") (pinfunction "2_2") (pintype "input"))
      (node (ref "C38") (pin "2") (pinfunction "2_2") (pintype "input"))
      (node (ref "C5") (pin "1") (pinfunction "1_1") (pintype "input"))
      (node (ref "C9") (pin "2") (pinfunction "2_2") (pintype "input"))
      (node (ref "H1") (pin "1") (pinfunction "1_1") (pintype "unspecified"))
      (node (ref "L1") (pin "1") (pinfunction "1_1") (pintype "unspecified"))
      (node (ref "R14") (pin "2") (pinfunction "2_2") (pintype "unspecified"))
      (node (ref "R16") (pin "2") (pinfunction "2_2") (pintype "unspecified"))
      (node (ref "R24") (pin "2") (pinfunction "2_2") (pintype "unspecified"))
      (node (ref "R25") (pin "2") (pinfunction "2_2") (pintype "unspecified"))
      (node (ref "R28") (pin "2") (pinfunction "2_2") (pintype "unspecified"))
      (node (ref "R38") (pin "1") (pinfunction "1_1") (pintype "unspecified"))
      (node (ref "R49") (pin "1") (pinfunction "1_1") (pintype "unspecified"))
      (node (ref "R5") (pin "2") (pinfunction "2_2") (pintype "unspecified"))
      (node (ref "R51") (pin "2") (pinfunction "2_2") (pintype "input"))
      (node (ref "R53") (pin "2") (pinfunction "2_2") (pintype "unspecified"))
      (node (ref "R6") (pin "2") (pinfunction "2_2") (pintype "unspecified"))
      (node (ref "R7") (pin "2") (pinfunction "2_2") (pintype "unspecified"))
      (node (ref "U10") (pin "8") (pinfunction "VCC_8") (pintype "unspecified"))
      (node (ref "U4") (pin "1") (pinfunction "VCC_1") (pintype "unspecified"))
      (node (ref "U5") (pin "5") (pinfunction "VCI_5") (pintype "input"))
      (node (ref "U6") (pin "4") (pinfunction "EN_4") (pintype "unspecified"))
      (node (ref "U6") (pin "5") (pinfunction "VIN_5") (pintype "unspecified"))
      (node (ref "U62") (pin "1") (pinfunction "VDD_1") (pintype "unspecified"))
      (node (ref "U63") (pin "2") (pinfunction "L/R_2") (pintype "unspecified"))
      (node (ref "U63") (pin "4") (pinfunction "VDD_4") (pintype "unspecified"))
      (node (ref "U65") (pin "8") (pinfunction "VCC_8") (pintype "unspecified"))
      (node (ref "U7") (pin "1") (pinfunction "SDO/SA0_1") (pintype "unspecified"))
      (node (ref "U7") (pin "12") (pinfunction "CS_12") (pintype "unspecified"))
      (node (ref "U7") (pin "5") (pinfunction "VDDIO_5") (pintype "unspecified"))
      (node (ref "U7") (pin "8") (pinfunction "VDD_8") (pintype "unspecified"))
      (node (ref "U8") (pin "15") (pinfunction "IOVDD_15") (pintype "unspecified"))
      (node (ref "U8") (pin "24") (pinfunction "IOVDD_24") (pintype "unspecified"))
      (node (ref "U8") (pin "29") (pinfunction "IOVDD_29") (pintype "unspecified"))
      (node (ref "U8") (pin "41") (pinfunction "IOVDD_41") (pintype "unspecified"))
      (node (ref "U8") (pin "5") (pinfunction "IOVDD_5") (pintype "unspecified"))
      (node (ref "U8") (pin "50") (pinfunction "IOVDD_50") (pintype "unspecified"))
      (node (ref "U8") (pin "59") (pinfunction "ADC_AVDD_59") (pintype "unspecified"))
      (node (ref "U8") (pin "60") (pinfunction "IOVDD_60") (pintype "unspecified"))
      (node (ref "U8") (pin "64") (pinfunction "VREG_VIN_64") (pintype "unspecified"))
      (node (ref "U8") (pin "68") (pinfunction "USB_OTP_VDD_68") (pintype "unspecified"))
      (node (ref "U8") (pin "69") (pinfunction "QSPI_IOVDD_69") (pintype "unspecified"))
      (node (ref "U8") (pin "76") (pinfunction "IOVDD_76") (pintype "unspecified"))
      (node (ref "U9") (pin "2") (pinfunction "VOUT(TAB)_2") (pintype "unspecified"))
      (node (ref "U9") (pin "4") (pinfunction "TAB_4") (pintype "unspecified"))
    )
    (net (code "3") (name "+5V_USB") (class "Default")
      (node (ref "C14") (pin "1") (pinfunction "1_1") (pintype "input"))
      (node (ref "R52") (pin "2") (pinfunction "2_2") (pintype "unspecified"))
      (node (ref "U9") (pin "3") (pinfunction "IN_3") (pintype "unspecified"))
      (node (ref "USB1") (pin "A4") (pinfunction "VBUS_A4") (pintype "unspecified"))
      (node (ref "USB1") (pin "A9") (pinfunction "VBUS_A9") (pintype "unspecified"))
    )
    (net (code "4") (name "+15V") (class "Default")
      (node (ref "C11") (pin "2") (pinfunction "2_2") (pintype "input"))
      (node (ref "C12") (pin "1") (pinfunction "1_1") (pintype "input"))
      (node (ref "C4") (pin "1") (pinfunction "1_1") (pintype "input"))
      (node (ref "D3") (pin "1") (pinfunction "K_1") (pintype "unspecified"))
      (node (ref "R27") (pin "2") (pinfunction "2_2") (pintype "unspecified"))
      (node (ref "U5") (pin "2") (pinfunction "VCC_2") (pintype "input"))
      (node (ref "U5") (pin "24") (pinfunction "VCC_24") (pintype "input"))
    )
    (net (code "5") (name "BOOTSEL") (class "Default")
      (node (ref "R36") (pin "2") (pinfunction "2_2") (pintype "unspecified"))
      (node (ref "SW1") (pin "3") (pinfunction "C_3") (pintype "unspecified"))
    )
    (net (code "6") (name "BUZZER") (class "Default")
      (node (ref "Q1") (pin "1") (pinfunction "G_1") (pintype "unspecified"))
      (node (ref "R2") (pin "1") (pinfunction "1_1") (pintype "unspecified"))
      (node (ref "U8") (pin "26") (pinfunction "GPIO25_26") (pintype "unspecified"))
    )
    (net (code "7") (name "CAPTOUCH_00") (class "Default")
      (node (ref "R1") (pin "1") (pinfunction "1_1") (pintype "unspecified"))
      (node (ref "TOUCH_FACE1") (pin "1") (pinfunction "1_1") (pintype "unspecified"))
      (node (ref "U8") (pin "28") (pinfunction "GPIO27_28") (pintype "unspecified"))
    )
    (net (code "8") (name "CAPTOUCH_01") (class "Default")
      (node (ref "R8") (pin "1") (pinfunction "1_1") (pintype "unspecified"))
      (node (ref "TOUCH_MENU1") (pin "1") (pinfunction "1_1") (pintype "unspecified"))
      (node (ref "U8") (pin "36") (pinfunction "GPIO28_36") (pintype "unspecified"))
    )
    (net (code "9") (name "CAPTOUCH_02") (class "Default")
      (node (ref "R9") (pin "1") (pinfunction "1_1") (pintype "unspecified"))
      (node (ref "TOUCH_YES1") (pin "1") (pinfunction "1_1") (pintype "unspecified"))
      (node (ref "U8") (pin "37") (pinfunction "GPIO29_37") (pintype "unspecified"))
    )
    (net (code "10") (name "CAPTOUCH_03") (class "Default")
      (node (ref "R10") (pin "1") (pinfunction "1_1") (pintype "unspecified"))
      (node (ref "TOUCH_NO1") (pin "1") (pinfunction "1_1") (pintype "unspecified"))
      (node (ref "U8") (pin "38") (pinfunction "GPIO30_38") (pintype "unspecified"))
    )
    (net (code "11") (name "CAPTOUCH_04") (class "Default")
      (node (ref "R11") (pin "1") (pinfunction "1_1") (pintype "unspecified"))
      (node (ref "TOUCH_CCW1") (pin "1") (pinfunction "1_1") (pintype "unspecified"))
      (node (ref "U8") (pin "39") (pinfunction "GPIO31_39") (pintype "unspecified"))
    )
    (net (code "12") (name "CAPTOUCH_05") (class "Default")
      (node (ref "R15") (pin "1") (pinfunction "1_1") (pintype "unspecified"))
      (node (ref "TOUCH_UP1") (pin "1") (pinfunction "1_1") (pintype "unspecified"))
      (node (ref "U8") (pin "40") (pinfunction "GPIO32_40") (pintype "unspecified"))
    )
    (net (code "13") (name "CAPTOUCH_06") (class "Default")
      (node (ref "R18") (pin "1") (pinfunction "1_1") (pintype "unspecified"))
      (node (ref "TOUCH_CW1") (pin "1") (pinfunction "1_1") (pintype "unspecified"))
      (node (ref "U8") (pin "42") (pinfunction "GPIO33_42") (pintype "unspecified"))
    )
    (net (code "14") (name "CAPTOUCH_07") (class "Default")
      (node (ref "R19") (pin "1") (pinfunction "1_1") (pintype "unspecified"))
      (node (ref "TOUCH_LEFT1") (pin "1") (pinfunction "1_1") (pintype "unspecified"))
      (node (ref "U8") (pin "43") (pinfunction "GPIO34_43") (pintype "unspecified"))
    )
    (net (code "15") (name "CAPTOUCH_08") (class "Default")
      (node (ref "R20") (pin "1") (pinfunction "1_1") (pintype "unspecified"))
      (node (ref "TOUCH_DOWN1") (pin "1") (pinfunction "1_1") (pintype "unspecified"))
      (node (ref "U8") (pin "44") (pinfunction "GPIO35_44") (pintype "unspecified"))
    )
    (net (code "16") (name "CAPTOUCH_09") (class "Default")
      (node (ref "R21") (pin "1") (pinfunction "1_1") (pintype "unspecified"))
      (node (ref "TOUCH_RIGHT1") (pin "1") (pinfunction "1_1") (pintype "unspecified"))
      (node (ref "U8") (pin "45") (pinfunction "GPIO36_45") (pintype "unspecified"))
    )
    (net (code "17") (name "CAPTOUCH_RET") (class "Default")
      (node (ref "R1") (pin "2") (pinfunction "2_2") (pintype "unspecified"))
      (node (ref "R10") (pin "2") (pinfunction "2_2") (pintype "unspecified"))
      (node (ref "R11") (pin "2") (pinfunction "2_2") (pintype "unspecified"))
      (node (ref "R15") (pin "2") (pinfunction "2_2") (pintype "unspecified"))
      (node (ref "R18") (pin "2") (pinfunction "2_2") (pintype "unspecified"))
      (node (ref "R19") (pin "2") (pinfunction "2_2") (pintype "unspecified"))
      (node (ref "R20") (pin "2") (pinfunction "2_2") (pintype "unspecified"))
      (node (ref "R21") (pin "2") (pinfunction "2_2") (pintype "unspecified"))
      (node (ref "R8") (pin "2") (pinfunction "2_2") (pintype "unspecified"))
      (node (ref "R9") (pin "2") (pinfunction "2_2") (pintype "unspecified"))
      (node (ref "U8") (pin "27") (pinfunction "GPIO26_27") (pintype "unspecified"))
    )
    (net (code "18") (name "CC1") (class "Default")
      (node (ref "R34") (pin "1") (pinfunction "1_1") (pintype "unspecified"))
      (node (ref "USB1") (pin "A5") (pinfunction "CC1_A5") (pintype "unspecified"))
    )
    (net (code "19") (name "CC2") (class "Default")
      (node (ref "R35") (pin "1") (pinfunction "1_1") (pintype "unspecified"))
      (node (ref "USB1") (pin "B5") (pinfunction "CC2_B5") (pintype "unspecified"))
    )
    (net (code "20") (name "DEBUG_G") (class "Default")
      (node (ref "U17") (pin "4") (pinfunction "4_4") (pintype "unspecified"))
      (node (ref "U8") (pin "47") (pinfunction "GPIO38_47") (pintype "unspecified"))
    )
    (net (code "21") (name "DEBUG_R") (class "Default")
      (node (ref "U17") (pin "2") (pinfunction "2_2") (pintype "unspecified"))
      (node (ref "U8") (pin "46") (pinfunction "GPIO37_46") (pintype "unspecified"))
    )
    (net (code "22") (name "DM") (class "Default")
      (node (ref "R33") (pin "2") (pinfunction "2_2") (pintype "input"))
      (node (ref "U8") (pin "66") (pinfunction "USB_DM_66") (pintype "unspecified"))
    )
    (net (code "23") (name "DMX") (class "Default")
      (node (ref "R33") (pin "1") (pinfunction "1_1") (pintype "input"))
      (node (ref "USB1") (pin "A7") (pinfunction "DN1_A7") (pintype "unspecified"))
      (node (ref "USB1") (pin "B7") (pinfunction "DN2_B7") (pintype "unspecified"))
    )
    (net (code "24") (name "DP") (class "Default")
      (node (ref "R32") (pin "2") (pinfunction "2_2") (pintype "input"))
      (node (ref "U8") (pin "67") (pinfunction "USB_DP_67") (pintype "unspecified"))
    )
    (net (code "25") (name "DPX") (class "Default")
      (node (ref "R32") (pin "1") (pinfunction "1_1") (pintype "input"))
      (node (ref "USB1") (pin "A6") (pinfunction "DP1_A6") (pintype "unspecified"))
      (node (ref "USB1") (pin "B6") (pinfunction "DP2_B6") (pintype "unspecified"))
    )
    (net (code "26") (name "GND") (class "Default")
      (node (ref "C1") (pin "1") (pinfunction "1_1") (pintype "unspecified"))
      (node (ref "C10") (pin "1") (pinfunction "1_1") (pintype "input"))
      (node (ref "C12") (pin "2") (pinfunction "2_2") (pintype "input"))
      (node (ref "C13") (pin "2") (pinfunction "2_2") (pintype "input"))
      (node (ref "C14") (pin "2") (pinfunction "2_2") (pintype "input"))
      (node (ref "C15") (pin "2") (pinfunction "2_2") (pintype "input"))
      (node (ref "C16") (pin "1") (pinfunction "1_1") (pintype "input"))
      (node (ref "C17") (pin "1") (pinfunction "1_1") (pintype "input"))
      (node (ref "C18") (pin "1") (pinfunction "1_1") (pintype "input"))
      (node (ref "C19") (pin "1") (pinfunction "1_1") (pintype "input"))
      (node (ref "C20") (pin "1") (pinfunction "1_1") (pintype "unspecified"))
      (node (ref "C21") (pin "1") (pinfunction "1_1") (pintype "unspecified"))
      (node (ref "C22") (pin "2") (pinfunction "2_2") (pintype "unspecified"))
      (node (ref "C23") (pin "1") (pinfunction "1_1") (pintype "input"))
      (node (ref "C24") (pin "1") (pinfunction "1_1") (pintype "input"))
      (node (ref "C25") (pin "1") (pinfunction "1_1") (pintype "input"))
      (node (ref "C26") (pin "1") (pinfunction "1_1") (pintype "input"))
      (node (ref "C27") (pin "1") (pinfunction "1_1") (pintype "input"))
      (node (ref "C28") (pin "1") (pinfunction "1_1") (pintype "input"))
      (node (ref "C29") (pin "1") (pinfunction "1_1") (pintype "input"))
      (node (ref "C3") (pin "2") (pinfunction "2_2") (pintype "input"))
      (node (ref "C30") (pin "1") (pinfunction "1_1") (pintype "input"))
      (node (ref "C31") (pin "1") (pinfunction "1_1") (pintype "input"))
      (node (ref "C32") (pin "1") (pinfunction "1_1") (pintype "input"))
      (node (ref "C33") (pin "1") (pinfunction "1_1") (pintype "input"))
      (node (ref "C34") (pin "2") (pinfunction "2_2") (pintype "unspecified"))
      (node (ref "C35") (pin "1") (pinfunction "1_1") (pintype "input"))
      (node (ref "C36") (pin "1") (pinfunction "1_1") (pintype "input"))
      (node (ref "C37") (pin "1") (pinfunction "1_1") (pintype "input"))
      (node (ref "C38") (pin "1") (pinfunction "1_1") (pintype "input"))
      (node (ref "C4") (pin "2") (pinfunction "2_2") (pintype "input"))
      (node (ref "C5") (pin "2") (pinfunction "2_2") (pintype "input"))
      (node (ref "C6") (pin "2") (pinfunction "2_2") (pintype "input"))
      (node (ref "C7") (pin "2") (pinfunction "2_2") (pintype "input"))
      (node (ref "C8") (pin "2") (pinfunction "2_2") (pintype "input"))
      (node (ref "C9") (pin "1") (pinfunction "1_1") (pintype "input"))
      (node (ref "CGQ1") (pin "1") (pinfunction "GND_1") (pintype "input"))
      (node (ref "CGQ1") (pin "2") (pinfunction "GND_2") (pintype "input"))
      (node (ref "D1") (pin "2") (pinfunction "A_2") (pintype "unspecified"))
      (node (ref "D2") (pin "2") (pinfunction "A_2") (pintype "unspecified"))
      (node (ref "H1") (pin "2") (pinfunction "2_2") (pintype "unspecified"))
      (node (ref "M1") (pin "3") (pinfunction "EP_3") (pintype "unspecified"))
      (node (ref "Q1") (pin "2") (pinfunction "S_2") (pintype "unspecified"))
      (node (ref "Q2") (pin "2") (pinfunction "S_2") (pintype "unspecified"))
      (node (ref "Q3") (pin "2") (pinfunction "S_2") (pintype "unspecified"))
      (node (ref "R2") (pin "2") (pinfunction "2_2") (pintype "unspecified"))
      (node (ref "R26") (pin "1") (pinfunction "1_1") (pintype "input"))
      (node (ref "R29") (pin "1") (pinfunction "1_1") (pintype "unspecified"))
      (node (ref "R3") (pin "2") (pinfunction "2_2") (pintype "unspecified"))
      (node (ref "R34") (pin "2") (pinfunction "2_2") (pintype "unspecified"))
      (node (ref "R35") (pin "2") (pinfunction "2_2") (pintype "unspecified"))
      (node (ref "R4") (pin "2") (pinfunction "2_2") (pintype "unspecified"))
      (node (ref "R45") (pin "2") (pinfunction "2_2") (pintype "unspecified"))
      (node (ref "R49") (pin "3") (pinfunction "3_3") (pintype "unspecified"))
      (node (ref "R54") (pin "1") (pinfunction "1_1") (pintype "input"))
      (node (ref "SW1") (pin "1") (pinfunction "A_1") (pintype "unspecified"))
      (node (ref "SW2") (pin "3") (pinfunction "C_3") (pintype "unspecified"))
      (node (ref "U10") (pin "4") (pinfunction "GND_4") (pintype "unspecified"))
      (node (ref "U11") (pin "2") (pinfunction "GND_2") (pintype "input"))
      (node (ref "U11") (pin "4") (pinfunction "GND_4") (pintype "input"))
      (node (ref "U17") (pin "3") (pinfunction "3_3") (pintype "unspecified"))
      (node (ref "U18") (pin "1") (pinfunction "1_1") (pintype "unspecified"))
      (node (ref "U18") (pin "3") (pinfunction "3_3") (pintype "unspecified"))
      (node (ref "U4") (pin "2") (pinfunction "GND_2") (pintype "unspecified"))
      (node (ref "U5") (pin "1") (pinfunction "GND_1") (pintype "input"))
      (node (ref "U5") (pin "14") (pinfunction "WR#_14") (pintype "input"))
      (node (ref "U5") (pin "15") (pinfunction "RD#_15") (pintype "input"))
      (node (ref "U5") (pin "18") (pinfunction "D2_18") (pintype "input"))
      (node (ref "U5") (pin "19") (pinfunction "D3_19") (pintype "input"))
      (node (ref "U5") (pin "20") (pinfunction "D4_20") (pintype "input"))
      (node (ref "U5") (pin "21") (pinfunction "D5_21") (pintype "input"))
      (node (ref "U5") (pin "22") (pinfunction "D6_22") (pintype "input"))
      (node (ref "U5") (pin "23") (pinfunction "D7_23") (pintype "input"))
      (node (ref "U5") (pin "25") (pinfunction "GND_25") (pintype "input"))
      (node (ref "U5") (pin "4") (pinfunction "GPIO_4") (pintype "input"))
      (node (ref "U5") (pin "7") (pinfunction "BS1_7") (pintype "input"))
      (node (ref "U5") (pin "8") (pinfunction "BS2_8") (pintype "input"))
      (node (ref "U5") (pin "9") (pinfunction "GND_9") (pintype "input"))
      (node (ref "U6") (pin "2") (pinfunction "GND_2") (pintype "unspecified"))
      (node (ref "U62") (pin "3") (pinfunction "GND_3") (pintype "unspecified"))
      (node (ref "U63") (pin "1") (pinfunction "GND_1") (pintype "unspecified"))
      (node (ref "U63") (pin "3") (pinfunction "GND_3") (pintype "unspecified"))
      (node (ref "U65") (pin "4") (pinfunction "VSS_4") (pintype "unspecified"))
      (node (ref "U66") (pin "2") (pinfunction "ANODE_2") (pintype "unspecified"))
      (node (ref "U66") (pin "3") (pinfunction "FB_3") (pintype "unspecified"))
      (node (ref "U69") (pin "1") (pinfunction "1_1") (pintype "unspecified"))
      (node (ref "U69") (pin "3") (pinfunction "3_3") (pintype "unspecified"))
      (node (ref "U7") (pin "2") (pinfunction "SDX_2") (pintype "unspecified"))
      (node (ref "U7") (pin "3") (pinfunction "SCX_3") (pintype "unspecified"))
      (node (ref "U7") (pin "6") (pinfunction "GND_6") (pintype "unspecified"))
      (node (ref "U7") (pin "7") (pinfunction "GND_7") (pintype "unspecified"))
      (node (ref "U8") (pin "62") (pinfunction "VREG_PGND_62") (pintype "unspecified"))
      (node (ref "U8") (pin "81") (pinfunction "GND_81") (pintype "unspecified"))
      (node (ref "U9") (pin "1") (pinfunction "ADJ(GND)_1") (pintype "unspecified"))
      (node (ref "USB1") (pin "0") (pinfunction "EH_0") (pintype "unspecified"))
      (node (ref "USB1") (pin "A1") (pinfunction "GND_A1") (pintype "unspecified"))
      (node (ref "USB1") (pin "A12") (pinfunction "GND_A12") (pintype "unspecified"))
    )
    (net (code "27") (name "HALL") (class "Default")
      (node (ref "C6") (pin "1") (pinfunction "1_1") (pintype "input"))
      (node (ref "U4") (pin "3") (pinfunction "OUT_3") (pintype "unspecified"))
      (node (ref "U8") (pin "52") (pinfunction "GPIO41_ADC1_52") (pintype "unspecified"))
    )
    (net (code "28") (name "IMU_INT1") (class "Default")
      (node (ref "U7") (pin "4") (pinfunction "INT1_4") (pintype "unspecified"))
    )
    (net (code "29") (name "IMU_INT2") (class "Default")
      (node (ref "U7") (pin "9") (pinfunction "INT2_9") (pintype "unspecified"))
    )
    (net (code "30") (name "IR_RXD") (class "Default")
      (node (ref "CGQ1") (pin "3") (pinfunction "VOUT_3") (pintype "input"))
      (node (ref "R16") (pin "1") (pinfunction "1_1") (pintype "unspecified"))
      (node (ref "U8") (pin "54") (pinfunction "GPIO43_ADC3_54") (pintype "unspecified"))
    )
    (net (code "31") (name "IR_TXD") (class "Default")
      (node (ref "Q2") (pin "1") (pinfunction "G_1") (pintype "unspecified"))
      (node (ref "R3") (pin "1") (pinfunction "1_1") (pintype "unspecified"))
      (node (ref "U8") (pin "25") (pinfunction "GPIO24_25") (pintype "unspecified"))
    )
    (net (code "32") (name "MAT00") (class "Default")
      (node (ref "U14") (pin "1") (pinfunction "1_1") (pintype "unspecified"))
      (node (ref "U14") (pin "3") (pinfunction "3_3") (pintype "unspecified"))
      (node (ref "U16") (pin "1") (pinfunction "1_1") (pintype "unspecified"))
      (node (ref "U16") (pin "3") (pinfunction "3_3") (pintype "unspecified"))
      (node (ref "U20") (pin "1") (pinfunction "1_1") (pintype "unspecified"))
      (node (ref "U20") (pin "3") (pinfunction "3_3") (pintype "unspecified"))
      (node (ref "U26") (pin "2") (pinfunction "2_2") (pintype "unspecified"))
      (node (ref "U26") (pin "4") (pinfunction "4_4") (pintype "unspecified"))
      (node (ref "U28") (pin "2") (pinfunction "2_2") (pintype "unspecified"))
      (node (ref "U28") (pin "4") (pinfunction "4_4") (pintype "unspecified"))
      (node (ref "U32") (pin "2") (pinfunction "2_2") (pintype "unspecified"))
      (node (ref "U32") (pin "4") (pinfunction "4_4") (pintype "unspecified"))
      (node (ref "U8") (pin "80") (pinfunction "GPIO3_80") (pintype "unspecified"))
    )
    (net (code "33") (name "MAT01") (class "Default")
      (node (ref "U13") (pin "1") (pinfunction "1_1") (pintype "unspecified"))
      (node (ref "U13") (pin "3") (pinfunction "3_3") (pintype "unspecified"))
      (node (ref "U15") (pin "1") (pinfunction "1_1") (pintype "unspecified"))
      (node (ref "U15") (pin "3") (pinfunction "3_3") (pintype "unspecified"))
      (node (ref "U21") (pin "1") (pinfunction "1_1") (pintype "unspecified"))
      (node (ref "U21") (pin "3") (pinfunction "3_3") (pintype "unspecified"))
      (node (ref "U27") (pin "2") (pinfunction "2_2") (pintype "unspecified"))
      (node (ref "U27") (pin "4") (pinfunction "4_4") (pintype "unspecified"))
      (node (ref "U29") (pin "2") (pinfunction "2_2") (pintype "unspecified"))
      (node (ref "U29") (pin "4") (pinfunction "4_4") (pintype "unspecified"))
      (node (ref "U33") (pin "2") (pinfunction "2_2") (pintype "unspecified"))
      (node (ref "U33") (pin "4") (pinfunction "4_4") (pintype "unspecified"))
      (node (ref "U8") (pin "2") (pinfunction "GPIO5_2") (pintype "unspecified"))
    )
    (net (code "34") (name "MAT02") (class "Default")
      (node (ref "R40") (pin "1") (pinfunction "1_1") (pintype "unspecified"))
      (node (ref "U12") (pin "1") (pinfunction "1_1") (pintype "unspecified"))
      (node (ref "U12") (pin "3") (pinfunction "3_3") (pintype "unspecified"))
      (node (ref "U22") (pin "1") (pinfunction "1_1") (pintype "unspecified"))
      (node (ref "U22") (pin "3") (pinfunction "3_3") (pintype "unspecified"))
      (node (ref "U30") (pin "2") (pinfunction "2_2") (pintype "unspecified"))
      (node (ref "U30") (pin "4") (pinfunction "4_4") (pintype "unspecified"))
      (node (ref "U34") (pin "2") (pinfunction "2_2") (pintype "unspecified"))
      (node (ref "U34") (pin "4") (pinfunction "4_4") (pintype "unspecified"))
      (node (ref "U8") (pin "3") (pinfunction "GPIO6_3") (pintype "unspecified"))
    )
    (net (code "35") (name "MAT02R") (class "Default")
      (node (ref "R40") (pin "2") (pinfunction "2_2") (pintype "unspecified"))
      (node (ref "U14") (pin "2") (pinfunction "2_2") (pintype "unspecified"))
      (node (ref "U15") (pin "2") (pinfunction "2_2") (pintype "unspecified"))
      (node (ref "U26") (pin "1") (pinfunction "1_1") (pintype "unspecified"))
      (node (ref "U27") (pin "1") (pinfunction "1_1") (pintype "unspecified"))
    )
    (net (code "36") (name "MAT03") (class "Default")
      (node (ref "U14") (pin "4") (pinfunction "4_4") (pintype "unspecified"))
      (node (ref "U15") (pin "4") (pinfunction "4_4") (pintype "unspecified"))
      (node (ref "U19") (pin "1") (pinfunction "1_1") (pintype "unspecified"))
      (node (ref "U19") (pin "3") (pinfunction "3_3") (pintype "unspecified"))
      (node (ref "U23") (pin "1") (pinfunction "1_1") (pintype "unspecified"))
      (node (ref "U23") (pin "3") (pinfunction "3_3") (pintype "unspecified"))
      (node (ref "U26") (pin "3") (pinfunction "3_3") (pintype "unspecified"))
      (node (ref "U27") (pin "3") (pinfunction "3_3") (pintype "unspecified"))
      (node (ref "U31") (pin "2") (pinfunction "2_2") (pintype "unspecified"))
      (node (ref "U31") (pin "4") (pinfunction "4_4") (pintype "unspecified"))
      (node (ref "U35") (pin "2") (pinfunction "2_2") (pintype "unspecified"))
      (node (ref "U35") (pin "4") (pinfunction "4_4") (pintype "unspecified"))
      (node (ref "U8") (pin "4") (pinfunction "GPIO7_4") (pintype "unspecified"))
    )
    (net (code "37") (name "MAT04") (class "Default")
      (node (ref "U12") (pin "4") (pinfunction "4_4") (pintype "unspecified"))
      (node (ref "U13") (pin "4") (pinfunction "4_4") (pintype "unspecified"))
      (node (ref "U16") (pin "4") (pinfunction "4_4") (pintype "unspecified"))
      (node (ref "U19") (pin "4") (pinfunction "4_4") (pintype "unspecified"))
      (node (ref "U24") (pin "1") (pinfunction "1_1") (pintype "unspecified"))
      (node (ref "U24") (pin "3") (pinfunction "3_3") (pintype "unspecified"))
      (node (ref "U28") (pin "3") (pinfunction "3_3") (pintype "unspecified"))
      (node (ref "U29") (pin "3") (pinfunction "3_3") (pintype "unspecified"))
      (node (ref "U30") (pin "3") (pinfunction "3_3") (pintype "unspecified"))
      (node (ref "U31") (pin "3") (pinfunction "3_3") (pintype "unspecified"))
      (node (ref "U36") (pin "2") (pinfunction "2_2") (pintype "unspecified"))
      (node (ref "U36") (pin "4") (pinfunction "4_4") (pintype "unspecified"))
      (node (ref "U8") (pin "1") (pinfunction "GPIO4_1") (pintype "unspecified"))
    )
    (net (code "38") (name "MAT05") (class "Default")
      (node (ref "R43") (pin "1") (pinfunction "1_1") (pintype "unspecified"))
      (node (ref "TP6") (pin "1") (pinfunction "1_1") (pintype "unspecified"))
      (node (ref "U25") (pin "1") (pinfunction "1_1") (pintype "unspecified"))
      (node (ref "U25") (pin "3") (pinfunction "3_3") (pintype "unspecified"))
      (node (ref "U37") (pin "2") (pinfunction "2_2") (pintype "unspecified"))
      (node (ref "U37") (pin "4") (pinfunction "4_4") (pintype "unspecified"))
      (node (ref "U8") (pin "78") (pinfunction "GPIO1_78") (pintype "unspecified"))
    )
    (net (code "39") (name "MAT05R") (class "Default")
      (node (ref "R43") (pin "2") (pinfunction "2_2") (pintype "unspecified"))
      (node (ref "U12") (pin "2") (pinfunction "2_2") (pintype "unspecified"))
      (node (ref "U13") (pin "2") (pinfunction "2_2") (pintype "unspecified"))
      (node (ref "U16") (pin "2") (pinfunction "2_2") (pintype "unspecified"))
      (node (ref "U19") (pin "2") (pinfunction "2_2") (pintype "unspecified"))
      (node (ref "U28") (pin "1") (pinfunction "1_1") (pintype "unspecified"))
      (node (ref "U29") (pin "1") (pinfunction "1_1") (pintype "unspecified"))
      (node (ref "U30") (pin "1") (pinfunction "1_1") (pintype "unspecified"))
      (node (ref "U31") (pin "1") (pinfunction "1_1") (pintype "unspecified"))
    )
    (net (code "40") (name "MAT06") (class "Default")
      (node (ref "U20") (pin "4") (pinfunction "4_4") (pintype "unspecified"))
      (node (ref "U21") (pin "4") (pinfunction "4_4") (pintype "unspecified"))
      (node (ref "U22") (pin "4") (pinfunction "4_4") (pintype "unspecified"))
      (node (ref "U23") (pin "4") (pinfunction "4_4") (pintype "unspecified"))
      (node (ref "U24") (pin "4") (pinfunction "4_4") (pintype "unspecified"))
      (node (ref "U25") (pin "4") (pinfunction "4_4") (pintype "unspecified"))
      (node (ref "U32") (pin "3") (pinfunction "3_3") (pintype "unspecified"))
      (node (ref "U33") (pin "3") (pinfunction "3_3") (pintype "unspecified"))
      (node (ref "U34") (pin "3") (pinfunction "3_3") (pintype "unspecified"))
      (node (ref "U35") (pin "3") (pinfunction "3_3") (pintype "unspecified"))
      (node (ref "U36") (pin "3") (pinfunction "3_3") (pintype "unspecified"))
      (node (ref "U37") (pin "3") (pinfunction "3_3") (pintype "unspecified"))
      (node (ref "U8") (pin "79") (pinfunction "GPIO2_79") (pintype "unspecified"))
    )
    (net (code "41") (name "MAT07") (class "Default")
      (node (ref "R44") (pin "1") (pinfunction "1_1") (pintype "unspecified"))
      (node (ref "TP5") (pin "1") (pinfunction "1_1") (pintype "unspecified"))
      (node (ref "U8") (pin "77") (pinfunction "GPIO0_77") (pintype "unspecified"))
    )
    (net (code "42") (name "MAT07R") (class "Default")
      (node (ref "R44") (pin "2") (pinfunction "2_2") (pintype "unspecified"))
      (node (ref "U20") (pin "2") (pinfunction "2_2") (pintype "unspecified"))
      (node (ref "U21") (pin "2") (pinfunction "2_2") (pintype "unspecified"))
      (node (ref "U22") (pin "2") (pinfunction "2_2") (pintype "unspecified"))
      (node (ref "U23") (pin "2") (pinfunction "2_2") (pintype "unspecified"))
      (node (ref "U24") (pin "2") (pinfunction "2_2") (pintype "unspecified"))
      (node (ref "U25") (pin "2") (pinfunction "2_2") (pintype "unspecified"))
      (node (ref "U32") (pin "1") (pinfunction "1_1") (pintype "unspecified"))
      (node (ref "U33") (pin "1") (pinfunction "1_1") (pintype "unspecified"))
      (node (ref "U34") (pin "1") (pinfunction "1_1") (pintype "unspecified"))
      (node (ref "U35") (pin "1") (pinfunction "1_1") (pintype "unspecified"))
      (node (ref "U36") (pin "1") (pinfunction "1_1") (pintype "unspecified"))
      (node (ref "U37") (pin "1") (pinfunction "1_1") (pintype "unspecified"))
    )
    (net (code "43") (name "MAT10") (class "Default")
      (node (ref "U44") (pin "2") (pinfunction "2_2") (pintype "unspecified"))
      (node (ref "U44") (pin "4") (pinfunction "4_4") (pintype "unspecified"))
      (node (ref "U49") (pin "2") (pinfunction "2_2") (pintype "unspecified"))
      (node (ref "U49") (pin "4") (pinfunction "4_4") (pintype "unspecified"))
      (node (ref "U50") (pin "1") (pinfunction "1_1") (pintype "unspecified"))
      (node (ref "U50") (pin "3") (pinfunction "3_3") (pintype "unspecified"))
      (node (ref "U52") (pin "1") (pinfunction "1_1") (pintype "unspecified"))
      (node (ref "U52") (pin "3") (pinfunction "3_3") (pintype "unspecified"))
      (node (ref "U58") (pin "2") (pinfunction "2_2") (pintype "unspecified"))
      (node (ref "U58") (pin "4") (pinfunction "4_4") (pintype "unspecified"))
      (node (ref "U61") (pin "1") (pinfunction "1_1") (pintype "unspecified"))
      (node (ref "U61") (pin "3") (pinfunction "3_3") (pintype "unspecified"))
      (node (ref "U8") (pin "17") (pinfunction "GPIO17_17") (pintype "unspecified"))
    )
    (net (code "44") (name "MAT11") (class "Default")
      (node (ref "U41") (pin "1") (pinfunction "1_1") (pintype "unspecified"))
      (node (ref "U41") (pin "3") (pinfunction "3_3") (pintype "unspecified"))
      (node (ref "U43") (pin "2") (pinfunction "2_2") (pintype "unspecified"))
      (node (ref "U43") (pin "4") (pinfunction "4_4") (pintype "unspecified"))
      (node (ref "U51") (pin "2") (pinfunction "2_2") (pintype "unspecified"))
      (node (ref "U51") (pin "4") (pinfunction "4_4") (pintype "unspecified"))
      (node (ref "U53") (pin "1") (pinfunction "1_1") (pintype "unspecified"))
      (node (ref "U53") (pin "3") (pinfunction "3_3") (pintype "unspecified"))
      (node (ref "U56") (pin "1") (pinfunction "1_1") (pintype "unspecified"))
      (node (ref "U56") (pin "3") (pinfunction "3_3") (pintype "unspecified"))
      (node (ref "U60") (pin "2") (pinfunction "2_2") (pintype "unspecified"))
      (node (ref "U60") (pin "4") (pinfunction "4_4") (pintype "unspecified"))
      (node (ref "U8") (pin "20") (pinfunction "GPIO20_20") (pintype "unspecified"))
    )
    (net (code "45") (name "MAT12") (class "Default")
      (node (ref "R48") (pin "1") (pinfunction "1_1") (pintype "unspecified"))
      (node (ref "U42") (pin "2") (pinfunction "2_2") (pintype "unspecified"))
      (node (ref "U42") (pin "4") (pinfunction "4_4") (pintype "unspecified"))
      (node (ref "U55") (pin "1") (pinfunction "1_1") (pintype "unspecified"))
      (node (ref "U55") (pin "3") (pinfunction "3_3") (pintype "unspecified"))
      (node (ref "U57") (pin "1") (pinfunction "1_1") (pintype "unspecified"))
      (node (ref "U57") (pin "3") (pinfunction "3_3") (pintype "unspecified"))
      (node (ref "U59") (pin "2") (pinfunction "2_2") (pintype "unspecified"))
      (node (ref "U59") (pin "4") (pinfunction "4_4") (pintype "unspecified"))
      (node (ref "U8") (pin "16") (pinfunction "GPIO16_16") (pintype "unspecified"))
    )
    (net (code "46") (name "MAT12R") (class "Default")
      (node (ref "R48") (pin "2") (pinfunction "2_2") (pintype "unspecified"))
      (node (ref "U43") (pin "1") (pinfunction "1_1") (pintype "unspecified"))
      (node (ref "U53") (pin "2") (pinfunction "2_2") (pintype "unspecified"))
      (node (ref "U58") (pin "1") (pinfunction "1_1") (pintype "unspecified"))
      (node (ref "U61") (pin "2") (pinfunction "2_2") (pintype "unspecified"))
    )
    (net (code "47") (name "MAT13") (class "Default")
      (node (ref "U39") (pin "1") (pinfunction "1_1") (pintype "unspecified"))
      (node (ref "U39") (pin "3") (pinfunction "3_3") (pintype "unspecified"))
      (node (ref "U43") (pin "3") (pinfunction "3_3") (pintype "unspecified"))
      (node (ref "U45") (pin "2") (pinfunction "2_2") (pintype "unspecified"))
      (node (ref "U45") (pin "4") (pinfunction "4_4") (pintype "unspecified"))
      (node (ref "U46") (pin "2") (pinfunction "2_2") (pintype "unspecified"))
      (node (ref "U46") (pin "4") (pinfunction "4_4") (pintype "unspecified"))
      (node (ref "U53") (pin "4") (pinfunction "4_4") (pintype "unspecified"))
      (node (ref "U54") (pin "1") (pinfunction "1_1") (pintype "unspecified"))
      (node (ref "U54") (pin "3") (pinfunction "3_3") (pintype "unspecified"))
      (node (ref "U58") (pin "3") (pinfunction "3_3") (pintype "unspecified"))
      (node (ref "U61") (pin "4") (pinfunction "4_4") (pintype "unspecified"))
      (node (ref "U8") (pin "21") (pinfunction "GPIO21_21") (pintype "unspecified"))
    )
    (net (code "48") (name "MAT14") (class "Default")
      (node (ref "U38") (pin "1") (pinfunction "1_1") (pintype "unspecified"))
      (node (ref "U38") (pin "3") (pinfunction "3_3") (pintype "unspecified"))
      (node (ref "U39") (pin "4") (pinfunction "4_4") (pintype "unspecified"))
      (node (ref "U42") (pin "3") (pinfunction "3_3") (pintype "unspecified"))
      (node (ref "U46") (pin "3") (pinfunction "3_3") (pintype "unspecified"))
      (node (ref "U48") (pin "2") (pinfunction "2_2") (pintype "unspecified"))
      (node (ref "U48") (pin "4") (pinfunction "4_4") (pintype "unspecified"))
      (node (ref "U49") (pin "3") (pinfunction "3_3") (pintype "unspecified"))
      (node (ref "U50") (pin "4") (pinfunction "4_4") (pintype "unspecified"))
      (node (ref "U51") (pin "3") (pinfunction "3_3") (pintype "unspecified"))
      (node (ref "U55") (pin "4") (pinfunction "4_4") (pintype "unspecified"))
      (node (ref "U56") (pin "4") (pinfunction "4_4") (pintype "unspecified"))
      (node (ref "U8") (pin "22") (pinfunction "GPIO22_22") (pintype "unspecified"))
    )
    (net (code "49") (name "MAT15") (class "Default")
      (node (ref "R47") (pin "1") (pinfunction "1_1") (pintype "unspecified"))
      (node (ref "U40") (pin "1") (pinfunction "1_1") (pintype "unspecified"))
      (node (ref "U40") (pin "3") (pinfunction "3_3") (pintype "unspecified"))
      (node (ref "U47") (pin "2") (pinfunction "2_2") (pintype "unspecified"))
      (node (ref "U47") (pin "4") (pinfunction "4_4") (pintype "unspecified"))
      (node (ref "U8") (pin "23") (pinfunction "GPIO23_23") (pintype "unspecified"))
    )
    (net (code "50") (name "MAT15R") (class "Default")
      (node (ref "R47") (pin "2") (pinfunction "2_2") (pintype "unspecified"))
      (node (ref "U39") (pin "2") (pinfunction "2_2") (pintype "unspecified"))
      (node (ref "U42") (pin "1") (pinfunction "1_1") (pintype "unspecified"))
      (node (ref "U46") (pin "1") (pinfunction "1_1") (pintype "unspecified"))
      (node (ref "U49") (pin "1") (pinfunction "1_1") (pintype "unspecified"))
      (node (ref "U50") (pin "2") (pinfunction "2_2") (pintype "unspecified"))
      (node (ref "U51") (pin "1") (pinfunction "1_1") (pintype "unspecified"))
      (node (ref "U55") (pin "2") (pinfunction "2_2") (pintype "unspecified"))
      (node (ref "U56") (pin "2") (pinfunction "2_2") (pintype "unspecified"))
    )
    (net (code "51") (name "MAT16") (class "Default")
      (node (ref "U38") (pin "4") (pinfunction "4_4") (pintype "unspecified"))
      (node (ref "U40") (pin "4") (pinfunction "4_4") (pintype "unspecified"))
      (node (ref "U41") (pin "4") (pinfunction "4_4") (pintype "unspecified"))
      (node (ref "U44") (pin "3") (pinfunction "3_3") (pintype "unspecified"))
      (node (ref "U45") (pin "3") (pinfunction "3_3") (pintype "unspecified"))
      (node (ref "U47") (pin "3") (pinfunction "3_3") (pintype "unspecified"))
      (node (ref "U48") (pin "3") (pinfunction "3_3") (pintype "unspecified"))
      (node (ref "U52") (pin "4") (pinfunction "4_4") (pintype "unspecified"))
      (node (ref "U54") (pin "4") (pinfunction "4_4") (pintype "unspecified"))
      (node (ref "U57") (pin "4") (pinfunction "4_4") (pintype "unspecified"))
      (node (ref "U59") (pin "3") (pinfunction "3_3") (pintype "unspecified"))
      (node (ref "U60") (pin "3") (pinfunction "3_3") (pintype "unspecified"))
      (node (ref "U8") (pin "19") (pinfunction "GPIO19_19") (pintype "unspecified"))
    )
    (net (code "52") (name "MAT17") (class "Default")
      (node (ref "R46") (pin "1") (pinfunction "1_1") (pintype "unspecified"))
      (node (ref "U8") (pin "18") (pinfunction "GPIO18_18") (pintype "unspecified"))
    )
    (net (code "53") (name "MAT17R") (class "Default")
      (node (ref "R46") (pin "2") (pinfunction "2_2") (pintype "unspecified"))
      (node (ref "U38") (pin "2") (pinfunction "2_2") (pintype "unspecified"))
      (node (ref "U40") (pin "2") (pinfunction "2_2") (pintype "unspecified"))
      (node (ref "U41") (pin "2") (pinfunction "2_2") (pintype "unspecified"))
      (node (ref "U44") (pin "1") (pinfunction "1_1") (pintype "unspecified"))
      (node (ref "U45") (pin "1") (pinfunction "1_1") (pintype "unspecified"))
      (node (ref "U47") (pin "1") (pinfunction "1_1") (pintype "unspecified"))
      (node (ref "U48") (pin "1") (pinfunction "1_1") (pintype "unspecified"))
      (node (ref "U52") (pin "2") (pinfunction "2_2") (pintype "unspecified"))
      (node (ref "U54") (pin "2") (pinfunction "2_2") (pintype "unspecified"))
      (node (ref "U57") (pin "2") (pinfunction "2_2") (pintype "unspecified"))
      (node (ref "U59") (pin "1") (pinfunction "1_1") (pintype "unspecified"))
      (node (ref "U60") (pin "1") (pinfunction "1_1") (pintype "unspecified"))
    )
    (net (code "54") (name "MIC_CLK") (class "Default")
      (node (ref "U63") (pin "6") (pinfunction "CLK_6") (pintype "unspecified"))
      (node (ref "U8") (pin "14") (pinfunction "GPIO15_14") (pintype "unspecified"))
    )
    (net (code "55") (name "MIC_DATA") (class "Default")
      (node (ref "U63") (pin "5") (pinfunction "DATA_5") (pintype "unspecified"))
      (node (ref "U8") (pin "13") (pinfunction "GPIO14_13") (pintype "unspecified"))
    )
    (net (code "56") (name "MOTOR") (class "Default")
      (node (ref "Q3") (pin "1") (pinfunction "G_1") (pintype "unspecified"))
      (node (ref "R4") (pin "1") (pinfunction "1_1") (pintype "unspecified"))
      (node (ref "U8") (pin "48") (pinfunction "GPIO39_48") (pintype "unspecified"))
    )
    (net (code "57") (name "Net-(BUZZER1-+)") (class "Default")
      (node (ref "BUZZER1") (pin "1") (pinfunction "+_1") (pintype "unspecified"))
      (node (ref "R5") (pin "1") (pinfunction "1_1") (pintype "unspecified"))
    )
    (net (code "58") (name "Net-(BUZZER1--)") (class "Default")
      (node (ref "BUZZER1") (pin "2") (pinfunction "-_2") (pintype "unspecified"))
      (node (ref "D1") (pin "1") (pinfunction "K_1") (pintype "unspecified"))
      (node (ref "Q1") (pin "3") (pinfunction "D_3") (pintype "unspecified"))
    )
    (net (code "59") (name "Net-(C18-Pad2)") (class "Default")
      (node (ref "C18") (pin "2") (pinfunction "2_2") (pintype "input"))
      (node (ref "R37") (pin "1") (pinfunction "1_1") (pintype "unspecified"))
      (node (ref "U11") (pin "3") (pinfunction "3_3") (pintype "input"))
    )
    (net (code "60") (name "Net-(CGQ1-VCC)") (class "Default")
      (node (ref "CGQ1") (pin "4") (pinfunction "VCC_4") (pintype "input"))
      (node (ref "R14") (pin "1") (pinfunction "1_1") (pintype "unspecified"))
    )
    (net (code "61") (name "Net-(D2-K)") (class "Default")
      (node (ref "D2") (pin "1") (pinfunction "K_1") (pintype "unspecified"))
      (node (ref "M1") (pin "2") (pinfunction "-_2") (pintype "unspecified"))
      (node (ref "Q3") (pin "3") (pinfunction "D_3") (pintype "unspecified"))
    )
    (net (code "62") (name "Net-(D3-A)") (class "Default")
      (node (ref "D3") (pin "2") (pinfunction "A_2") (pintype "unspecified"))
      (node (ref "L1") (pin "2") (pinfunction "2_2") (pintype "unspecified"))
      (node (ref "U6") (pin "1") (pinfunction "SW_1") (pintype "unspecified"))
    )
    (net (code "63") (name "Net-(H1-Pad5)") (class "Default")
      (node (ref "H1") (pin "5") (pinfunction "5_5") (pintype "unspecified"))
      (node (ref "R30") (pin "2") (pinfunction "2_2") (pintype "unspecified"))
    )
    (net (code "64") (name "Net-(H1-Pad6)") (class "Default")
      (node (ref "H1") (pin "6") (pinfunction "6_6") (pintype "unspecified"))
      (node (ref "R31") (pin "2") (pinfunction "2_2") (pintype "unspecified"))
    )
    (net (code "65") (name "Net-(M1-+)") (class "Default")
      (node (ref "M1") (pin "1") (pinfunction "+_1") (pintype "unspecified"))
      (node (ref "R6") (pin "1") (pinfunction "1_1") (pintype "unspecified"))
    )
    (net (code "66") (name "Net-(Q2-D)") (class "Default")
      (node (ref "Q2") (pin "3") (pinfunction "D_3") (pintype "unspecified"))
      (node (ref "U1") (pin "1") (pinfunction "K_1") (pintype "unspecified"))
      (node (ref "U2") (pin "1") (pinfunction "K_1") (pintype "unspecified"))
      (node (ref "U3") (pin "1") (pinfunction "K_1") (pintype "unspecified"))
    )
    (net (code "67") (name "Net-(R45-Pad1)") (class "Default")
      (node (ref "R45") (pin "1") (pinfunction "1_1") (pintype "unspecified"))
      (node (ref "U17") (pin "1") (pinfunction "1_1") (pintype "unspecified"))
    )
    (net (code "68") (name "Net-(R52-Pad1)") (class "Default")
      (node (ref "R52") (pin "1") (pinfunction "1_1") (pintype "unspecified"))
      (node (ref "U18") (pin "2") (pinfunction "2_2") (pintype "unspecified"))
    )
    (net (code "69") (name "Net-(R53-Pad1)") (class "Default")
      (node (ref "R53") (pin "1") (pinfunction "1_1") (pintype "unspecified"))
      (node (ref "U18") (pin "4") (pinfunction "4_4") (pintype "unspecified"))
    )
    (net (code "70") (name "Net-(SW2-A)") (class "Default")
      (node (ref "R39") (pin "2") (pinfunction "2_2") (pintype "unspecified"))
      (node (ref "SW2") (pin "1") (pinfunction "A_1") (pintype "unspecified"))
    )
    (net (code "71") (name "Net-(U1-A)") (class "Default")
      (node (ref "U1") (pin "2") (pinfunction "A_2") (pintype "unspecified"))
      (node (ref "U2") (pin "2") (pinfunction "A_2") (pintype "unspecified"))
      (node (ref "U67") (pin "2") (pinfunction "2_2") (pintype "input"))
    )
    (net (code "72") (name "Net-(U3-A)") (class "Default")
      (node (ref "R7") (pin "1") (pinfunction "1_1") (pintype "unspecified"))
      (node (ref "U3") (pin "2") (pinfunction "A_2") (pintype "unspecified"))
      (node (ref "U67") (pin "1") (pinfunction "1_1") (pintype "input"))
    )
    (net (code "73") (name "Net-(U5-IREF)") (class "Default")
      (node (ref "R26") (pin "2") (pinfunction "2_2") (pintype "input"))
      (node (ref "U5") (pin "10") (pinfunction "IREF_10") (pintype "input"))
    )
    (net (code "74") (name "Net-(U5-RES#)") (class "Default")
      (node (ref "R28") (pin "1") (pinfunction "1_1") (pintype "unspecified"))
      (node (ref "U5") (pin "12") (pinfunction "RES#_12") (pintype "input"))
    )
    (net (code "75") (name "Net-(U5-VCOMH)") (class "Default")
      (node (ref "C7") (pin "1") (pinfunction "1_1") (pintype "input"))
      (node (ref "U5") (pin "3") (pinfunction "VCOMH_3") (pintype "input"))
    )
    (net (code "76") (name "Net-(U5-VDD)") (class "Default")
      (node (ref "C8") (pin "1") (pinfunction "1_1") (pintype "input"))
      (node (ref "U5") (pin "6") (pinfunction "VDD_6") (pintype "input"))
    )
    (net (code "77") (name "Net-(U6-FB)") (class "Default")
      (node (ref "C11") (pin "1") (pinfunction "1_1") (pintype "input"))
      (node (ref "R27") (pin "1") (pinfunction "1_1") (pintype "unspecified"))
      (node (ref "R29") (pin "2") (pinfunction "2_2") (pintype "unspecified"))
      (node (ref "R54") (pin "2") (pinfunction "2_2") (pintype "input"))
      (node (ref "U6") (pin "3") (pinfunction "FB_3") (pintype "unspecified"))
    )
    (net (code "78") (name "Net-(U65-GPO(OD))") (class "Default")
      (node (ref "TP1") (pin "1") (pinfunction "1_1") (pintype "unspecified"))
      (node (ref "U65") (pin "7") (pinfunction "GPO(OD)_7") (pintype "unspecified"))
    )
    (net (code "79") (name "OLED_CS") (class "Default")
      (node (ref "U5") (pin "11") (pinfunction "CS#_11") (pintype "input"))
      (node (ref "U8") (pin "7") (pinfunction "GPIO9_7") (pintype "unspecified"))
    )
    (net (code "80") (name "OLED_DC") (class "Default")
      (node (ref "U5") (pin "13") (pinfunction "D/C_13") (pintype "input"))
      (node (ref "U8") (pin "6") (pinfunction "GPIO8_6") (pintype "unspecified"))
    )
    (net (code "81") (name "OLED_MOSI") (class "Default")
      (node (ref "U5") (pin "17") (pinfunction "D1_17") (pintype "input"))
      (node (ref "U8") (pin "9") (pinfunction "GPIO11_9") (pintype "unspecified"))
    )
    (net (code "82") (name "OLED_SCK") (class "Default")
      (node (ref "U5") (pin "16") (pinfunction "D0_16") (pintype "input"))
      (node (ref "U8") (pin "8") (pinfunction "GPIO10_8") (pintype "unspecified"))
    )
    (net (code "83") (name "QSPI_SCLK") (class "Default")
      (node (ref "U10") (pin "6") (pinfunction "CLK_6") (pintype "unspecified"))
      (node (ref "U8") (pin "71") (pinfunction "QSPI_SCLK_71") (pintype "unspecified"))
    )
    (net (code "84") (name "QSPI_SD0") (class "Default")
      (node (ref "U10") (pin "5") (pinfunction "DI(IO0)_5") (pintype "unspecified"))
      (node (ref "U8") (pin "72") (pinfunction "QSPI_SD0_72") (pintype "unspecified"))
    )
    (net (code "85") (name "QSPI_SD1") (class "Default")
      (node (ref "U10") (pin "2") (pinfunction "DO(IO1)_2") (pintype "unspecified"))
      (node (ref "U8") (pin "74") (pinfunction "QSPI_SD1_74") (pintype "unspecified"))
    )
    (net (code "86") (name "QSPI_SD2") (class "Default")
      (node (ref "U10") (pin "3") (pinfunction "WP#(IO2)_3") (pintype "unspecified"))
      (node (ref "U8") (pin "73") (pinfunction "QSPI_SD2_73") (pintype "unspecified"))
    )
    (net (code "87") (name "QSPI_SD3") (class "Default")
      (node (ref "U10") (pin "7") (pinfunction "HOLD#orRESET#(IO3)_7") (pintype "unspecified"))
      (node (ref "U8") (pin "70") (pinfunction "QSPI_SD3_70") (pintype "unspecified"))
    )
    (net (code "88") (name "QSPI_SS") (class "Default")
      (node (ref "R36") (pin "1") (pinfunction "1_1") (pintype "unspecified"))
      (node (ref "U10") (pin "1") (pinfunction "CS#_1") (pintype "unspecified"))
      (node (ref "U8") (pin "75") (pinfunction "QSPI_SS_75") (pintype "unspecified"))
    )
    (net (code "89") (name "SAO_GPIO_1") (class "Default")
      (node (ref "R30") (pin "1") (pinfunction "1_1") (pintype "unspecified"))
      (node (ref "U8") (pin "55") (pinfunction "GPIO44_ADC4_55") (pintype "unspecified"))
    )
    (net (code "90") (name "SAO_GPIO_2") (class "Default")
      (node (ref "R31") (pin "1") (pinfunction "1_1") (pintype "unspecified"))
      (node (ref "U8") (pin "56") (pinfunction "GPIO45_ADC5_56") (pintype "unspecified"))
    )
    (net (code "91") (name "SAO_I2C_SCL") (class "Default")
      (node (ref "H1") (pin "4") (pinfunction "4_4") (pintype "unspecified"))
      (node (ref "U8") (pin "58") (pinfunction "GPIO47_ADC7_58") (pintype "unspecified"))
    )
    (net (code "92") (name "SAO_I2C_SDA") (class "Default")
      (node (ref "H1") (pin "3") (pinfunction "3_3") (pintype "unspecified"))
      (node (ref "U8") (pin "57") (pinfunction "GPIO46_ADC6_57") (pintype "unspecified"))
    )
    (net (code "93") (name "SCREW") (class "Default")
      (node (ref "R49") (pin "2") (pinfunction "2_2") (pintype "unspecified"))
      (node (ref "U8") (pin "53") (pinfunction "GPIO42_ADC2_53") (pintype "unspecified"))
    )
    (net (code "94") (name "SEN_I2C_SCL") (class "Default")
      (node (ref "R24") (pin "1") (pinfunction "1_1") (pintype "unspecified"))
      (node (ref "U62") (pin "4") (pinfunction "SCL_4") (pintype "unspecified"))
      (node (ref "U65") (pin "6") (pinfunction "SCL_6") (pintype "unspecified"))
      (node (ref "U7") (pin "13") (pinfunction "SCL_13") (pintype "unspecified"))
      (node (ref "U8") (pin "12") (pinfunction "GPIO13_12") (pintype "unspecified"))
    )
    (net (code "95") (name "SEN_I2C_SDA") (class "Default")
      (node (ref "R25") (pin "1") (pinfunction "1_1") (pintype "unspecified"))
      (node (ref "U62") (pin "6") (pinfunction "SDA_6") (pintype "unspecified"))
      (node (ref "U65") (pin "5") (pinfunction "SDA_5") (pintype "unspecified"))
      (node (ref "U7") (pin "14") (pinfunction "SDA_14") (pintype "unspecified"))
      (node (ref "U8") (pin "11") (pinfunction "GPIO12_11") (pintype "unspecified"))
    )
    (net (code "96") (name "SWCLK") (class "Default")
      (node (ref "TP3") (pin "1") (pinfunction "1_1") (pintype "unspecified"))
      (node (ref "U8") (pin "33") (pinfunction "SWCLK_33") (pintype "unspecified"))
    )
    (net (code "97") (name "SWDIO") (class "Default")
      (node (ref "TP4") (pin "1") (pinfunction "1_1") (pintype "unspecified"))
      (node (ref "U8") (pin "34") (pinfunction "SWDIO_34") (pintype "unspecified"))
    )
    (net (code "98") (name "VREG_AVDD") (class "Default")
      (node (ref "C20") (pin "2") (pinfunction "2_2") (pintype "unspecified"))
      (node (ref "R38") (pin "2") (pinfunction "2_2") (pintype "unspecified"))
      (node (ref "U8") (pin "61") (pinfunction "VREG_AVDD_61") (pintype "unspecified"))
    )
    (net (code "99") (name "VREG_LX") (class "Default")
      (node (ref "L2") (pin "1") (pinfunction "1_1") (pintype "unspecified"))
      (node (ref "U8") (pin "63") (pinfunction "VREG_LX_63") (pintype "unspecified"))
    )
    (net (code "100") (name "V_EH") (class "Default")
      (node (ref "U65") (pin "1") (pinfunction "V_EH_1") (pintype "unspecified"))
      (node (ref "U69") (pin "2") (pinfunction "2_2") (pintype "unspecified"))
    )
    (net (code "101") (name "V_REF") (class "Default")
      (node (ref "R51") (pin "1") (pinfunction "1_1") (pintype "input"))
      (node (ref "U66") (pin "1") (pinfunction "CATHODE_1") (pintype "unspecified"))
      (node (ref "U8") (pin "49") (pinfunction "GPIO40_ADC0_49") (pintype "unspecified"))
    )
    (net (code "102") (name "XIN") (class "Default")
      (node (ref "C19") (pin "2") (pinfunction "2_2") (pintype "input"))
      (node (ref "U11") (pin "1") (pinfunction "1_1") (pintype "input"))
      (node (ref "U8") (pin "30") (pinfunction "XIN_30") (pintype "unspecified"))
    )
    (net (code "103") (name "XOUT") (class "Default")
      (node (ref "R37") (pin "2") (pinfunction "2_2") (pintype "unspecified"))
      (node (ref "U8") (pin "31") (pinfunction "XOUT_31") (pintype "unspecified"))
    )
    (net (code "104") (name "unconnected-(BUZZER1-Pad3)") (class "Default")
      (node (ref "BUZZER1") (pin "3") (pinfunction "3_3") (pintype "unspecified+no_connect"))
    )
    (net (code "105") (name "unconnected-(BUZZER1-Pad4)") (class "Default")
      (node (ref "BUZZER1") (pin "4") (pinfunction "4_4") (pintype "unspecified+no_connect"))
    )
    (net (code "106") (name "unconnected-(SW1-B-Pad2)") (class "Default")
      (node (ref "SW1") (pin "2") (pinfunction "B_2") (pintype "unspecified+no_connect"))
    )
    (net (code "107") (name "unconnected-(SW1-D-Pad4)") (class "Default")
      (node (ref "SW1") (pin "4") (pinfunction "D_4") (pintype "unspecified+no_connect"))
    )
    (net (code "108") (name "unconnected-(SW2-B-Pad2)") (class "Default")
      (node (ref "SW2") (pin "2") (pinfunction "B_2") (pintype "unspecified+no_connect"))
    )
    (net (code "109") (name "unconnected-(SW2-D-Pad4)") (class "Default")
      (node (ref "SW2") (pin "4") (pinfunction "D_4") (pintype "unspecified+no_connect"))
    )
    (net (code "110") (name "unconnected-(U7-NC-Pad10)") (class "Default")
      (node (ref "U7") (pin "10") (pinfunction "NC_10") (pintype "unspecified+no_connect"))
    )
    (net (code "111") (name "unconnected-(U7-NC-Pad11)") (class "Default")
      (node (ref "U7") (pin "11") (pinfunction "NC_11") (pintype "unspecified+no_connect"))
    )
    (net (code "112") (name "unconnected-(U62-INT-Pad5)") (class "Default")
      (node (ref "U62") (pin "5") (pinfunction "INT_5") (pintype "unspecified+no_connect"))
    )
    (net (code "113") (name "unconnected-(U62-NC-Pad2)") (class "Default")
      (node (ref "U62") (pin "2") (pinfunction "NC_2") (pintype "unspecified+no_connect"))
    )
    (net (code "114") (name "unconnected-(U65-AC0-Pad2)") (class "Default")
      (node (ref "U65") (pin "2") (pinfunction "AC0_2") (pintype "unspecified"))
    )
    (net (code "115") (name "unconnected-(U65-AC1-Pad3)") (class "Default")
      (node (ref "U65") (pin "3") (pinfunction "AC1_3") (pintype "unspecified"))
    )
    (net (code "116") (name "unconnected-(U65-EP-Pad9)") (class "Default")
      (node (ref "U65") (pin "9") (pinfunction "EP_9") (pintype "unspecified+no_connect"))
    )
    (net (code "117") (name "unconnected-(U68-Pad1)") (class "Default")
      (node (ref "U68") (pin "1") (pinfunction "1_1") (pintype "input"))
    )
    (net (code "118") (name "unconnected-(U68-Pad2)") (class "Default")
      (node (ref "U68") (pin "2") (pinfunction "2_2") (pintype "input"))
    )
    (net (code "119") (name "unconnected-(U69-Pad4)") (class "Default")
      (node (ref "U69") (pin "4") (pinfunction "4_4") (pintype "unspecified+no_connect"))
    )
    (net (code "120") (name "unconnected-(USB1-SBU1-PadA8)") (class "Default")
      (node (ref "USB1") (pin "A8") (pinfunction "SBU1_A8") (pintype "unspecified+no_connect"))
    )
    (net (code "121") (name "unconnected-(USB1-SBU2-PadB8)") (class "Default")
      (node (ref "USB1") (pin "B8") (pinfunction "SBU2_B8") (pintype "unspecified+no_connect"))
    )
    (net (code "122") (name "~RESET") (class "Default")
      (node (ref "R39") (pin "1") (pinfunction "1_1") (pintype "unspecified"))
      (node (ref "U8") (pin "35") (pinfunction "RUN_35") (pintype "unspecified"))
    )
  )
)
